# EasyBMS.net
KiCad netlist of a schematic drawn in EAGLE
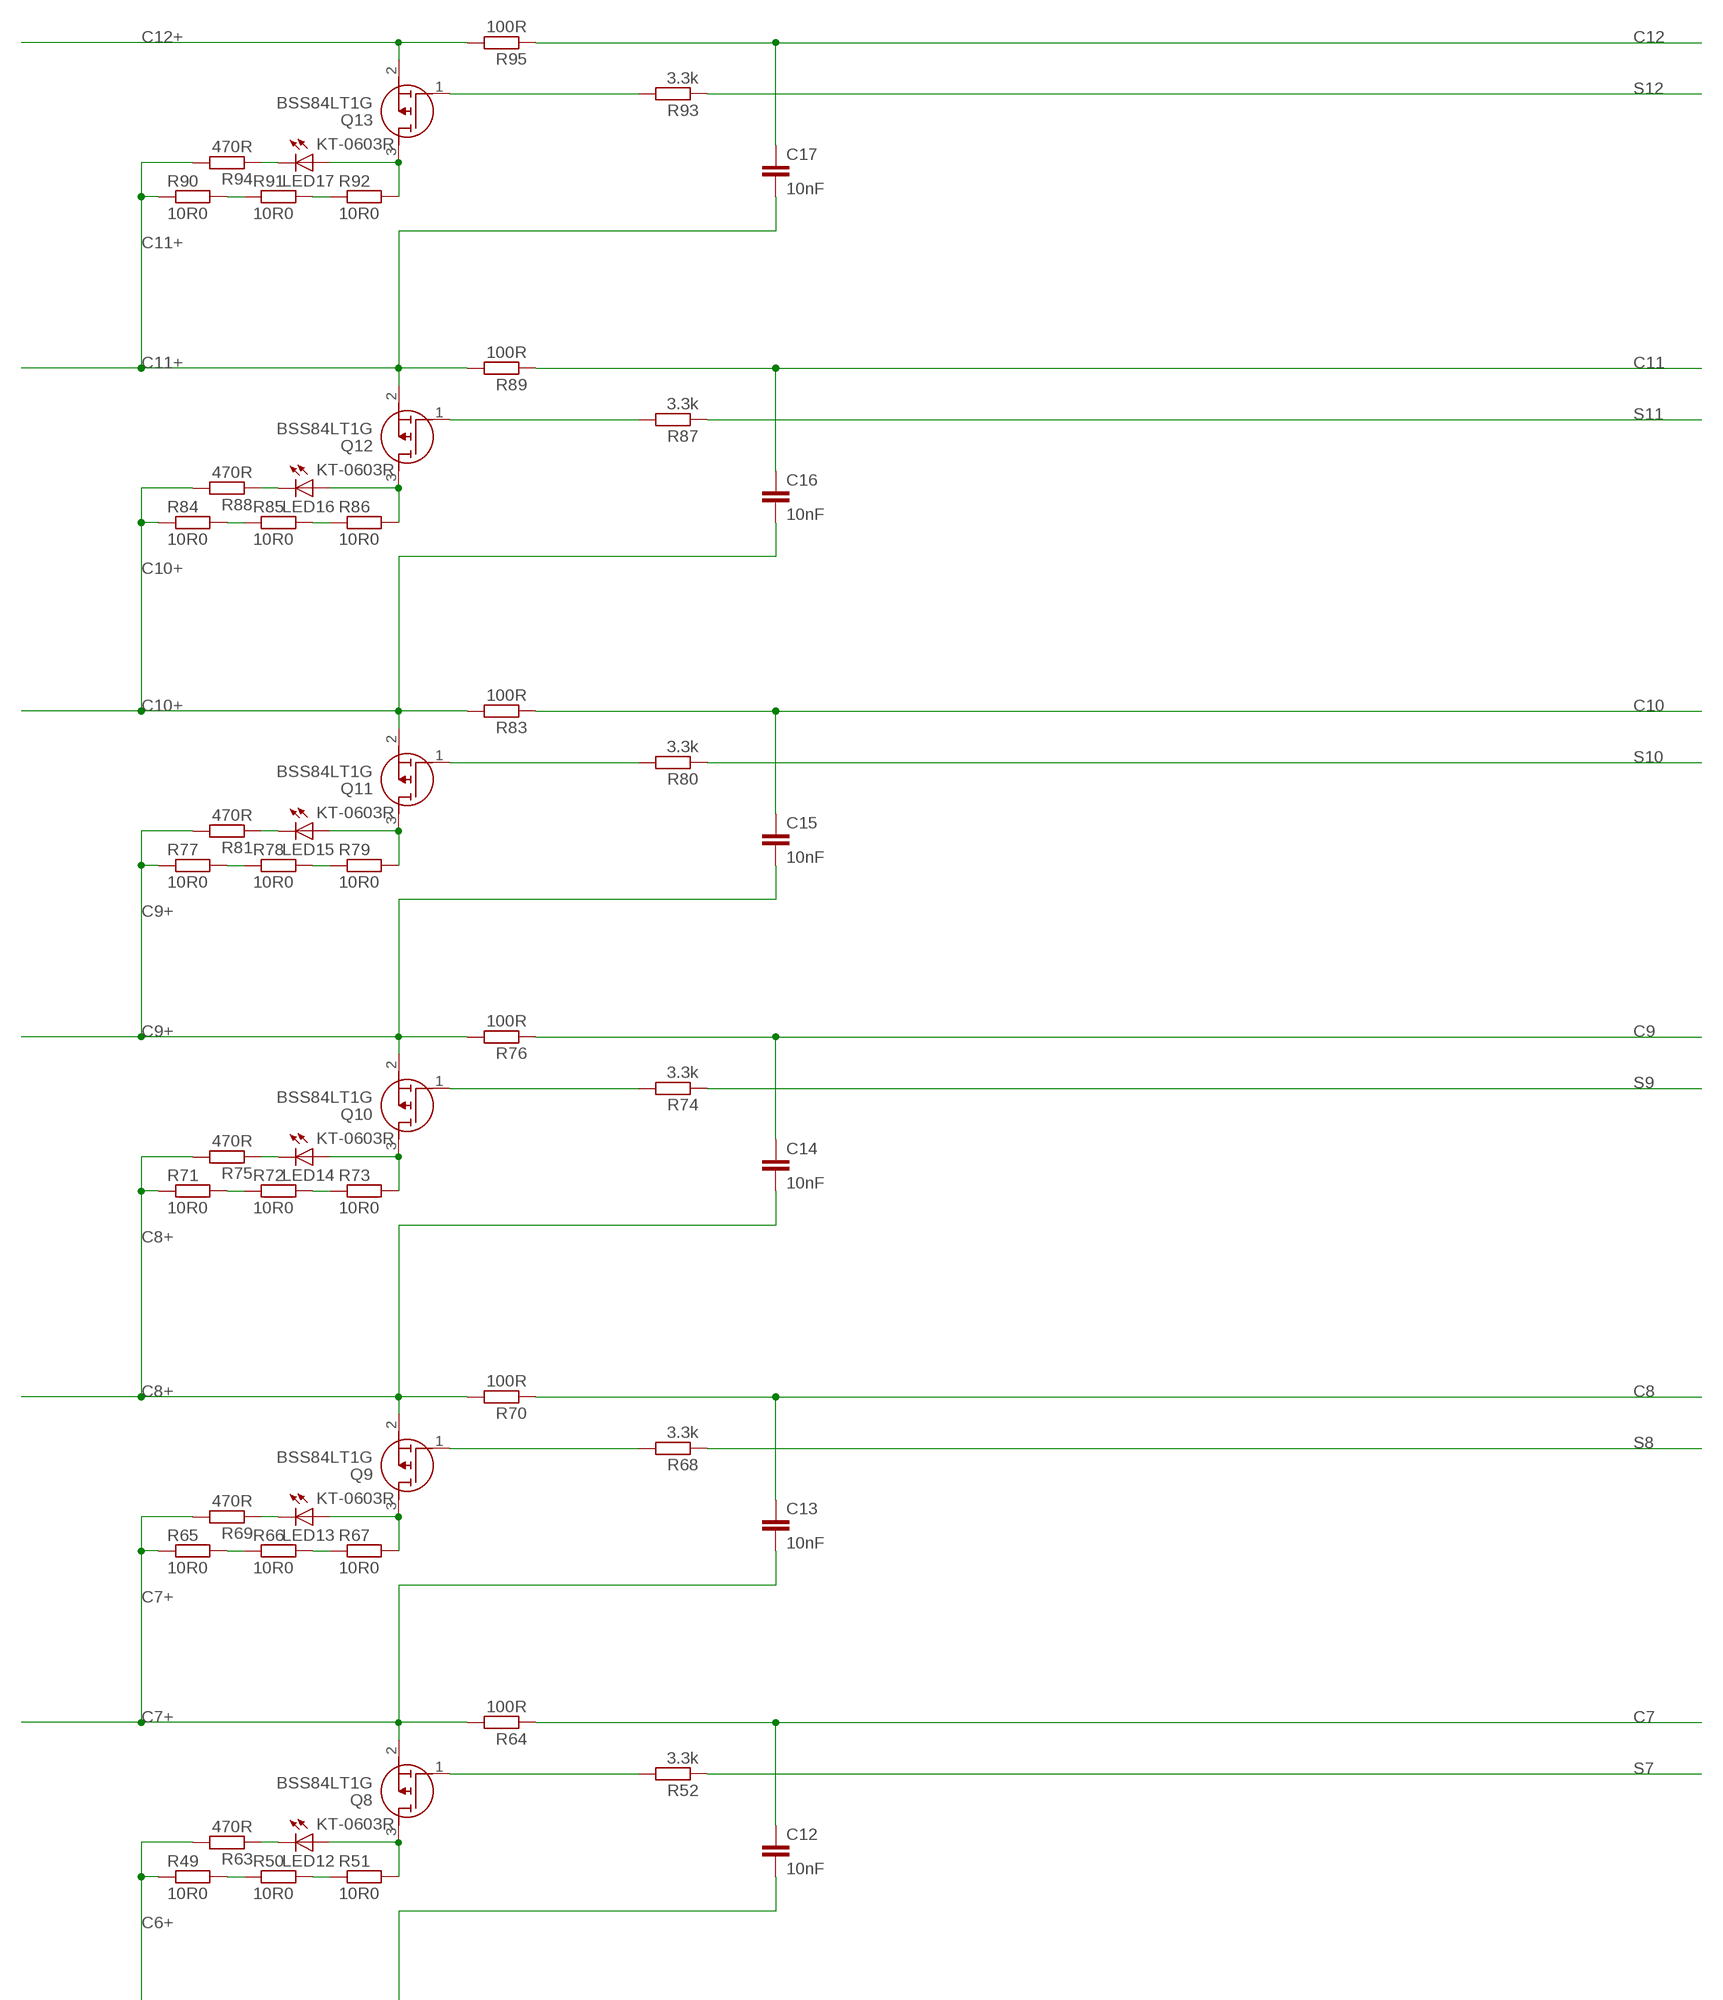
[diagram p0: schematic, sheet 1, part 1 of 3]
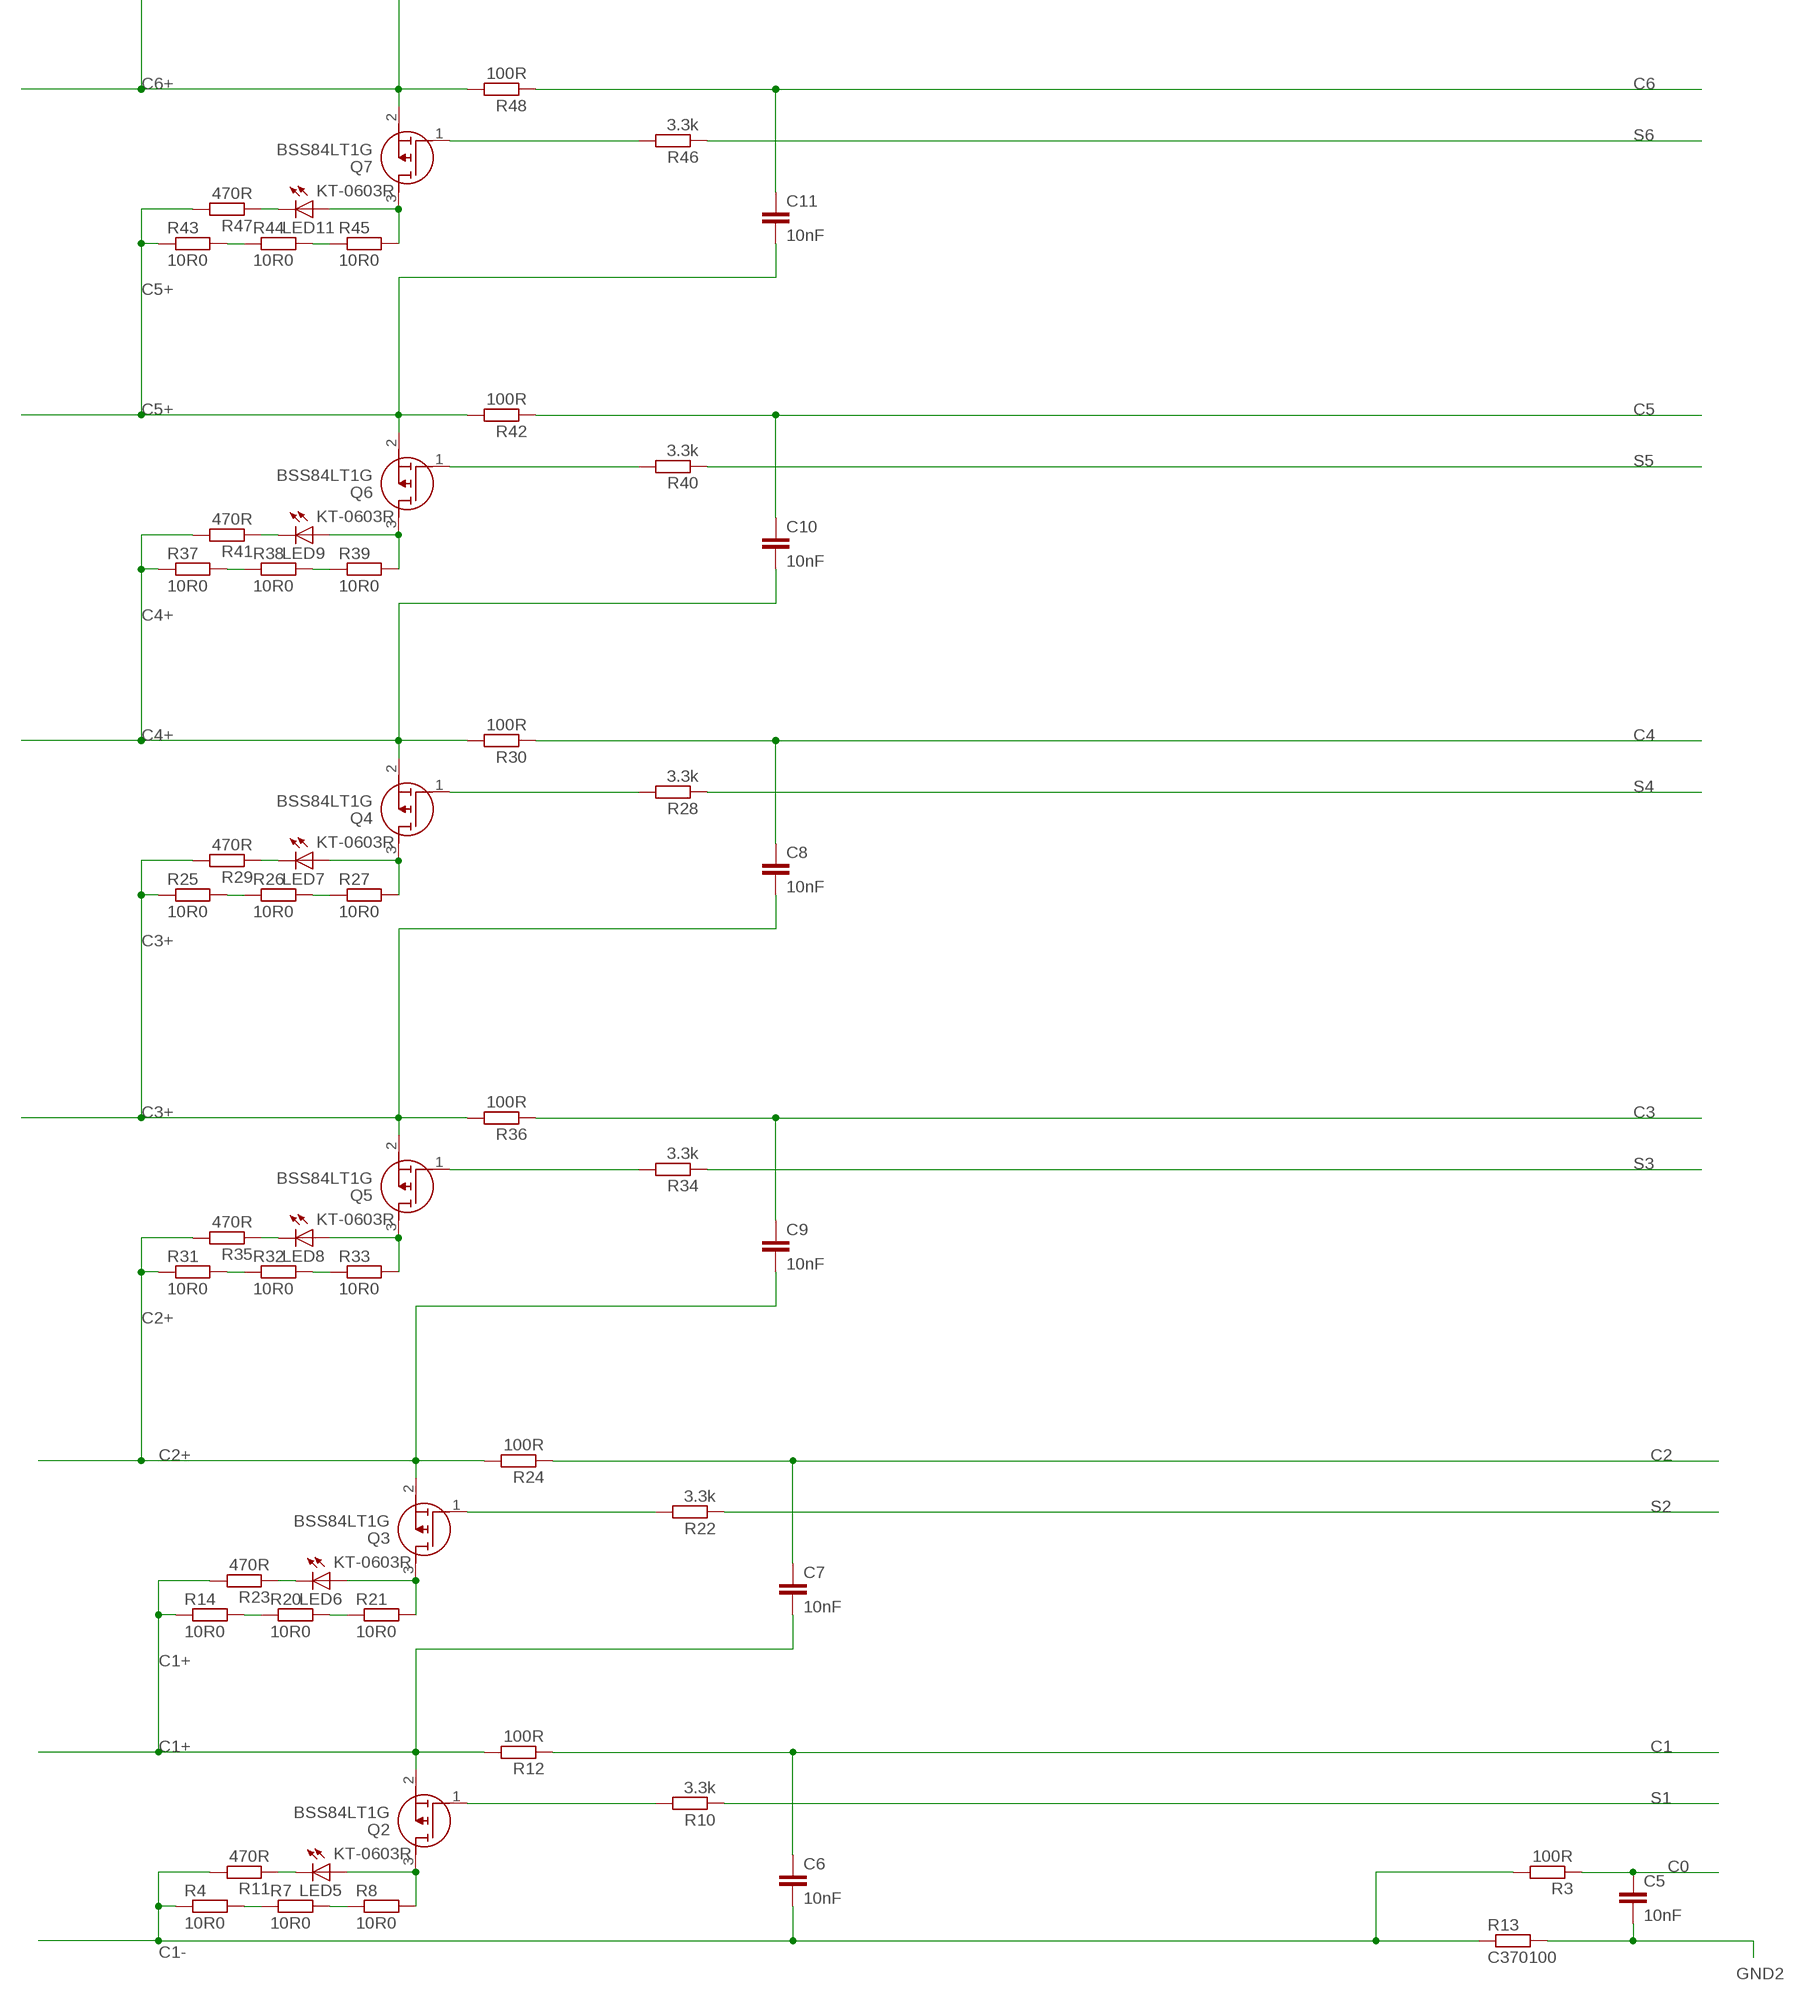
[diagram p1: schematic, sheet 1, part 2 of 3]
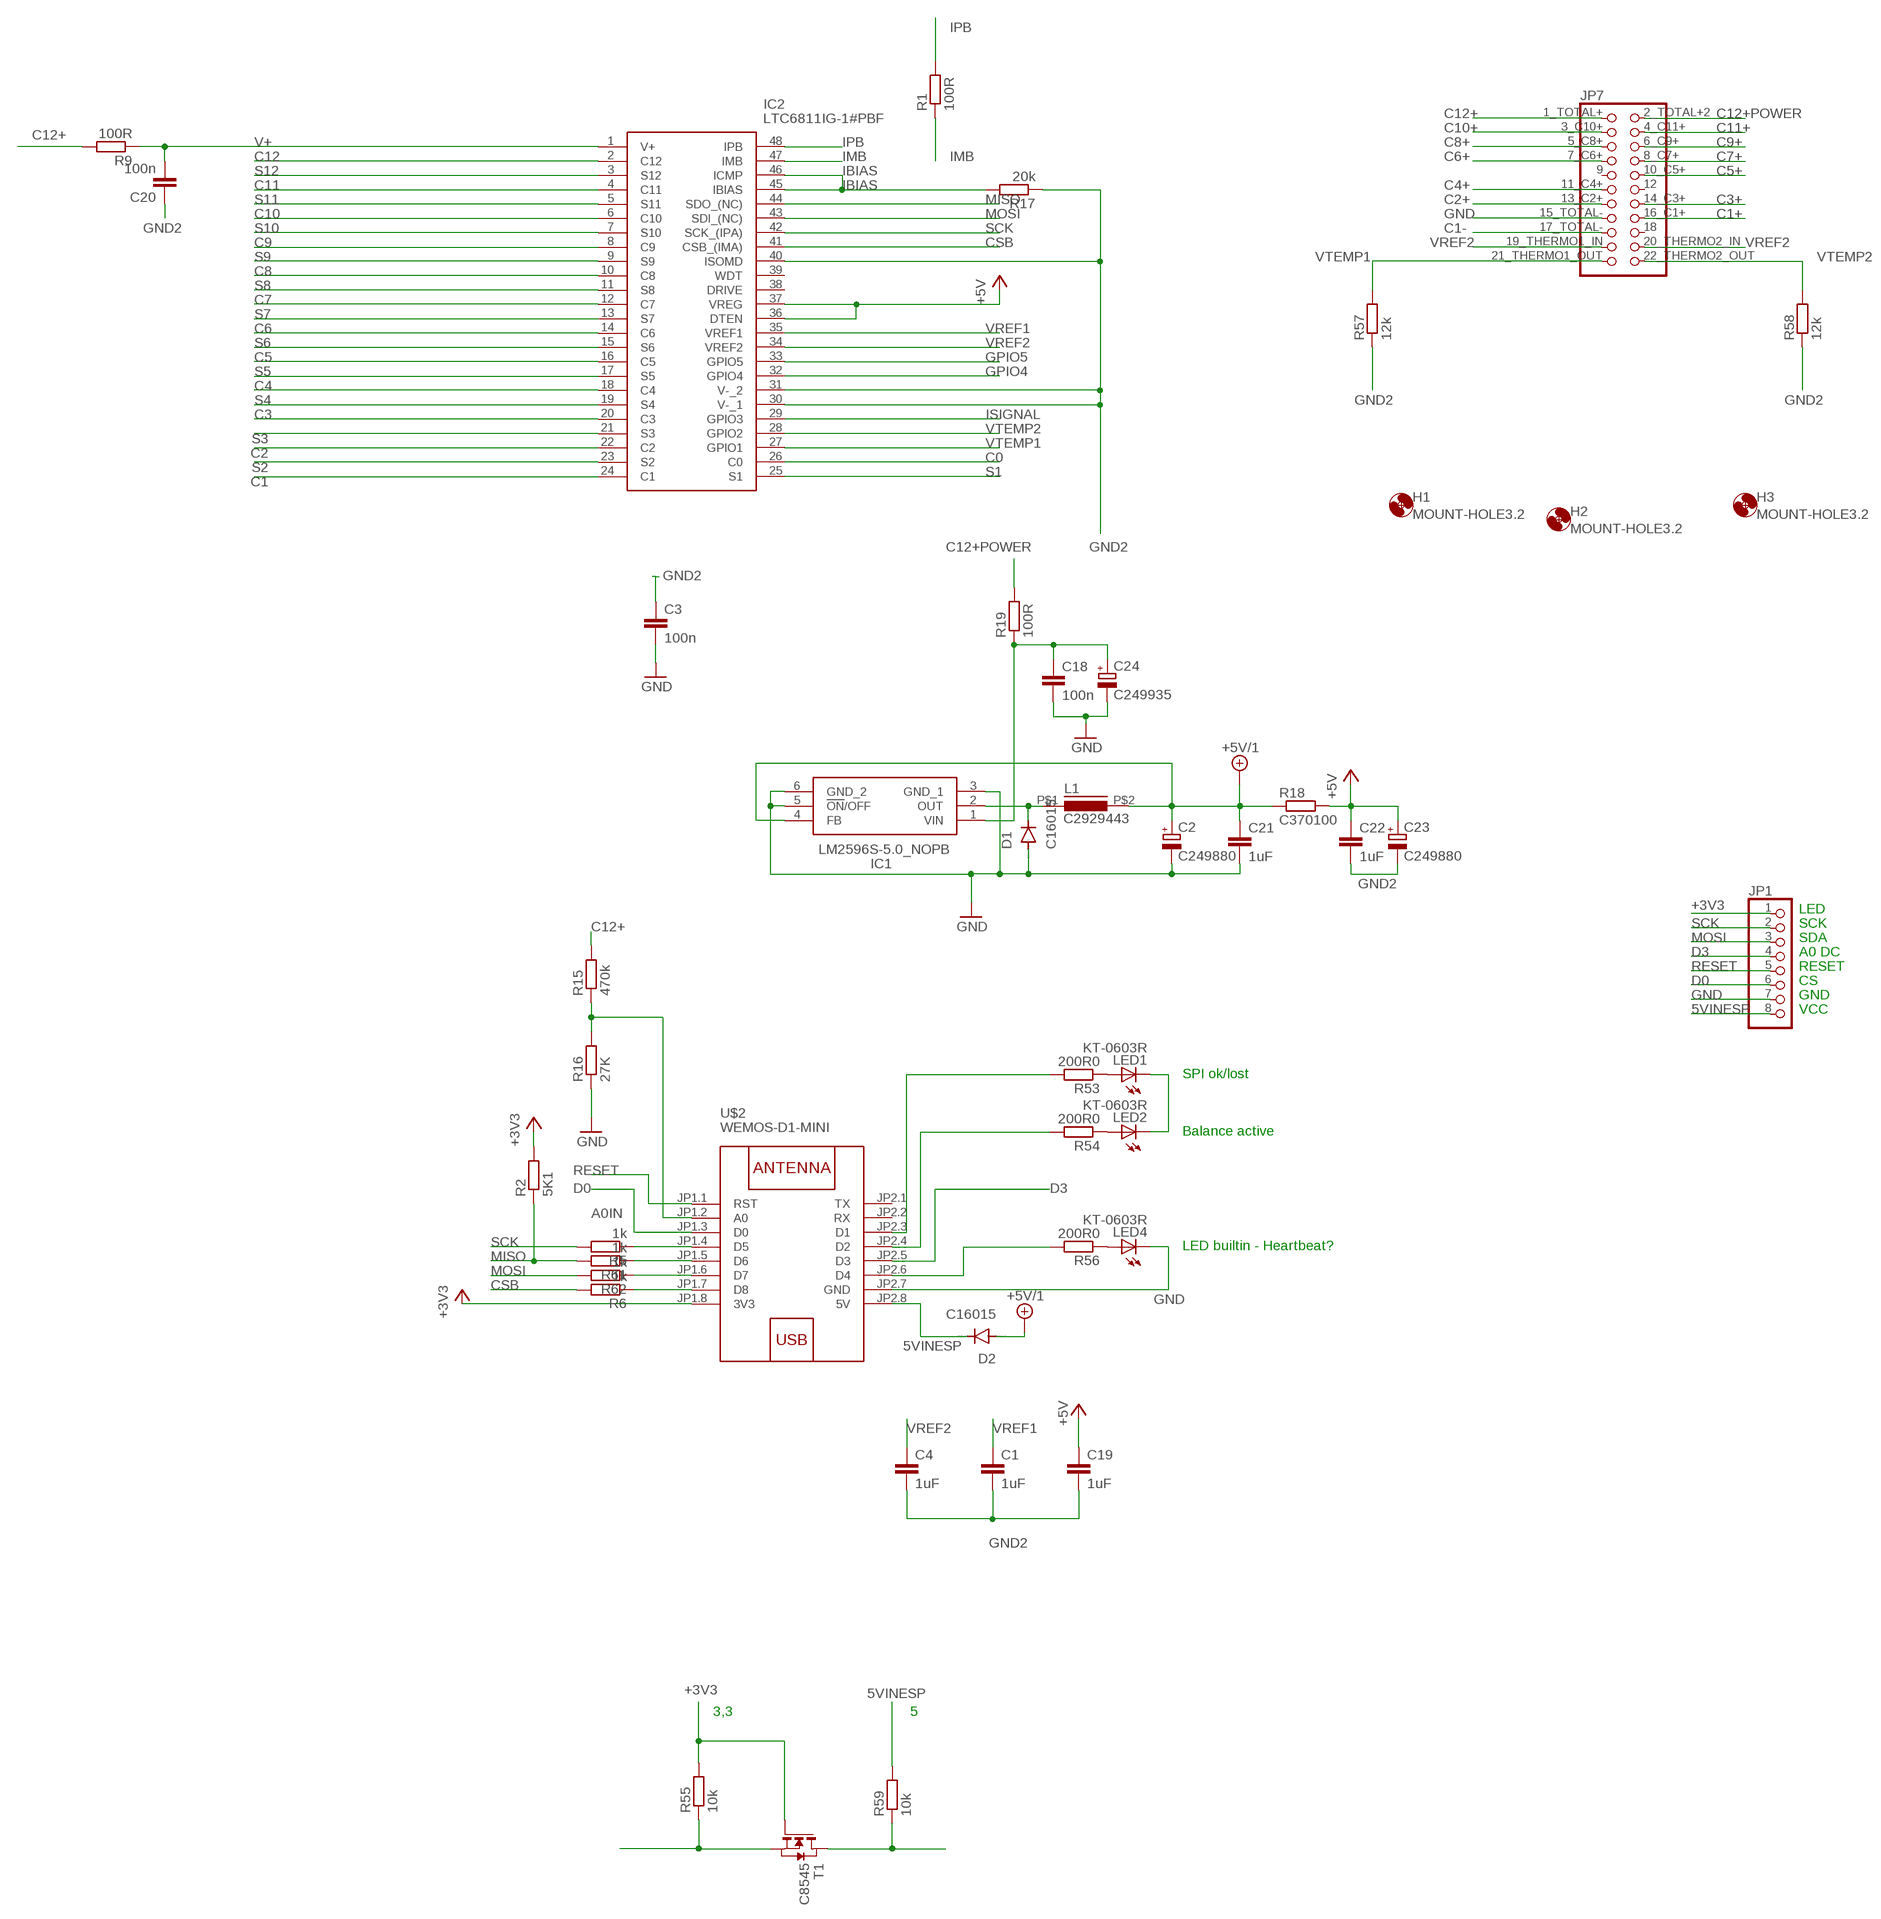
[diagram p2: schematic, sheet 1, part 3 of 3]

(export (version "E")
  (design (tool "Eeschema 10.0.6"))
  (components
    (comp (ref "C1")
      (value "1uF")
      (footprint "eagle-import:C1206")
      (libsource (lib "eagle-import") (part "C-EUC1206"))
    )
    (comp (ref "C2")
      (value "C249880")
      (footprint "eagle-import:UD-8X10_NICHICON")
      (libsource (lib "eagle-import") (part "CPOL-EUUD-8X10"))
    )
    (comp (ref "C3")
      (value "100n")
      (footprint "eagle-import:C0402")
      (libsource (lib "eagle-import") (part "C-EUC0402"))
    )
    (comp (ref "C4")
      (value "1uF")
      (footprint "eagle-import:C1206")
      (libsource (lib "eagle-import") (part "C-EUC1206"))
    )
    (comp (ref "C5")
      (value "10nF")
      (footprint "eagle-import:C0402")
      (libsource (lib "eagle-import") (part "C-EUC0402"))
    )
    (comp (ref "C6")
      (value "10nF")
      (footprint "eagle-import:C0402")
      (libsource (lib "eagle-import") (part "C-EUC0402"))
    )
    (comp (ref "C7")
      (value "10nF")
      (footprint "eagle-import:C0402")
      (libsource (lib "eagle-import") (part "C-EUC0402"))
    )
    (comp (ref "C8")
      (value "10nF")
      (footprint "eagle-import:C0402")
      (libsource (lib "eagle-import") (part "C-EUC0402"))
    )
    (comp (ref "C9")
      (value "10nF")
      (footprint "eagle-import:C0402")
      (libsource (lib "eagle-import") (part "C-EUC0402"))
    )
    (comp (ref "C10")
      (value "10nF")
      (footprint "eagle-import:C0402")
      (libsource (lib "eagle-import") (part "C-EUC0402"))
    )
    (comp (ref "C11")
      (value "10nF")
      (footprint "eagle-import:C0402")
      (libsource (lib "eagle-import") (part "C-EUC0402"))
    )
    (comp (ref "C12")
      (value "10nF")
      (footprint "eagle-import:C0402")
      (libsource (lib "eagle-import") (part "C-EUC0402"))
    )
    (comp (ref "C13")
      (value "10nF")
      (footprint "eagle-import:C0402")
      (libsource (lib "eagle-import") (part "C-EUC0402"))
    )
    (comp (ref "C14")
      (value "10nF")
      (footprint "eagle-import:C0402")
      (libsource (lib "eagle-import") (part "C-EUC0402"))
    )
    (comp (ref "C15")
      (value "10nF")
      (footprint "eagle-import:C0402")
      (libsource (lib "eagle-import") (part "C-EUC0402"))
    )
    (comp (ref "C16")
      (value "10nF")
      (footprint "eagle-import:C0402")
      (libsource (lib "eagle-import") (part "C-EUC0402"))
    )
    (comp (ref "C17")
      (value "10nF")
      (footprint "eagle-import:C0402")
      (libsource (lib "eagle-import") (part "C-EUC0402"))
    )
    (comp (ref "C18")
      (value "100n")
      (footprint "eagle-import:C0402")
      (libsource (lib "eagle-import") (part "C-EUC0402"))
    )
    (comp (ref "C19")
      (value "1uF")
      (footprint "eagle-import:C1206")
      (libsource (lib "eagle-import") (part "C-EUC1206"))
    )
    (comp (ref "C20")
      (value "100n")
      (footprint "eagle-import:C0402")
      (libsource (lib "eagle-import") (part "C-EUC0402"))
    )
    (comp (ref "C21")
      (value "1uF")
      (footprint "eagle-import:C1206")
      (libsource (lib "eagle-import") (part "C-EUC1206"))
    )
    (comp (ref "C22")
      (value "1uF")
      (footprint "eagle-import:C1206")
      (libsource (lib "eagle-import") (part "C-EUC1206"))
    )
    (comp (ref "C23")
      (value "C249880")
      (footprint "eagle-import:UD-8X10_NICHICON")
      (libsource (lib "eagle-import") (part "CPOL-EUUD-8X10"))
    )
    (comp (ref "C24")
      (value "C249935")
      (footprint "eagle-import:WCAP-ASLI_16X17(DXL)")
      (libsource (lib "eagle-import") (part "VZH471M1JTR-1616"))
    )
    (comp (ref "D1")
      (value "C16015")
      (footprint "eagle-import:DO214AC")
      (libsource (lib "eagle-import") (part "DIODE-DO214AC"))
    )
    (comp (ref "D2")
      (value "C16015")
      (footprint "eagle-import:DO214AC")
      (libsource (lib "eagle-import") (part "DIODE-DO214AC"))
    )
    (comp (ref "H1")
      (value "MOUNT-HOLE3.2")
      (footprint "eagle-import:3,2")
      (libsource (lib "eagle-import") (part "MOUNT-HOLE3.2"))
    )
    (comp (ref "H2")
      (value "MOUNT-HOLE3.2")
      (footprint "eagle-import:3,2")
      (libsource (lib "eagle-import") (part "MOUNT-HOLE3.2"))
    )
    (comp (ref "H3")
      (value "MOUNT-HOLE3.2")
      (footprint "eagle-import:3,2")
      (libsource (lib "eagle-import") (part "MOUNT-HOLE3.2"))
    )
    (comp (ref "IC1")
      (value "LM2596S-5.0_NOPB")
      (footprint "eagle-import:KTT0005B")
      (fields
        (field (name "MANUFACTURER_PART_NUMBER") "LM2596S-5.0/NOPB")
        (field (name "MOUSER_PART_NUMBER") "926-LM2596S-5.0/NOPB")
      )
      (libsource (lib "eagle-import") (part "LM2596S-5.0_NOPB"))
    )
    (comp (ref "IC2")
      (value "LTC6811IG-1#PBF")
      (footprint "eagle-import:SOP50P780X200-48N")
      (fields (field (name "MOUSER_PART_NUMBER") "584-LTC6811IG-1#PBF"))
      (libsource (lib "eagle-import") (part "LTC6811IG-1#PBF"))
    )
    (comp (ref "JP1")
      (value "PINHD-1X8")
      (footprint "eagle-import:1X08")
      (libsource (lib "eagle-import") (part "PINHD-1X8"))
    )
    (comp (ref "JP7")
      (value "PINHD-2X11_MEB12S")
      (footprint "eagle-import:2X11_MEB12S")
      (libsource (lib "eagle-import") (part "PINHD-2X11_MEB12S"))
    )
    (comp (ref "L1")
      (value "C2929443")
      (footprint "eagle-import:CY75-100UH")
      (libsource (lib "eagle-import") (part "CY75-100UH"))
    )
    (comp (ref "LED1")
      (value "KT-0603R")
      (footprint "eagle-import:CHIPLED_0603")
      (libsource (lib "eagle-import") (part "LEDCHIPLED_0603"))
    )
    (comp (ref "LED2")
      (value "KT-0603R")
      (footprint "eagle-import:CHIPLED_0603")
      (libsource (lib "eagle-import") (part "LEDCHIPLED_0603"))
    )
    (comp (ref "LED4")
      (value "KT-0603R")
      (footprint "eagle-import:CHIPLED_0603")
      (libsource (lib "eagle-import") (part "LEDCHIPLED_0603"))
    )
    (comp (ref "LED5")
      (value "KT-0603R")
      (footprint "eagle-import:CHIPLED_0603")
      (libsource (lib "eagle-import") (part "LEDCHIPLED_0603"))
    )
    (comp (ref "LED6")
      (value "KT-0603R")
      (footprint "eagle-import:CHIPLED_0603")
      (libsource (lib "eagle-import") (part "LEDCHIPLED_0603"))
    )
    (comp (ref "LED7")
      (value "KT-0603R")
      (footprint "eagle-import:CHIPLED_0603")
      (libsource (lib "eagle-import") (part "LEDCHIPLED_0603"))
    )
    (comp (ref "LED8")
      (value "KT-0603R")
      (footprint "eagle-import:CHIPLED_0603")
      (libsource (lib "eagle-import") (part "LEDCHIPLED_0603"))
    )
    (comp (ref "LED9")
      (value "KT-0603R")
      (footprint "eagle-import:CHIPLED_0603")
      (libsource (lib "eagle-import") (part "LEDCHIPLED_0603"))
    )
    (comp (ref "LED11")
      (value "KT-0603R")
      (footprint "eagle-import:CHIPLED_0603")
      (libsource (lib "eagle-import") (part "LEDCHIPLED_0603"))
    )
    (comp (ref "LED12")
      (value "KT-0603R")
      (footprint "eagle-import:CHIPLED_0603")
      (libsource (lib "eagle-import") (part "LEDCHIPLED_0603"))
    )
    (comp (ref "LED13")
      (value "KT-0603R")
      (footprint "eagle-import:CHIPLED_0603")
      (libsource (lib "eagle-import") (part "LEDCHIPLED_0603"))
    )
    (comp (ref "LED14")
      (value "KT-0603R")
      (footprint "eagle-import:CHIPLED_0603")
      (libsource (lib "eagle-import") (part "LEDCHIPLED_0603"))
    )
    (comp (ref "LED15")
      (value "KT-0603R")
      (footprint "eagle-import:CHIPLED_0603")
      (libsource (lib "eagle-import") (part "LEDCHIPLED_0603"))
    )
    (comp (ref "LED16")
      (value "KT-0603R")
      (footprint "eagle-import:CHIPLED_0603")
      (libsource (lib "eagle-import") (part "LEDCHIPLED_0603"))
    )
    (comp (ref "LED17")
      (value "KT-0603R")
      (footprint "eagle-import:CHIPLED_0603")
      (libsource (lib "eagle-import") (part "LEDCHIPLED_0603"))
    )
    (comp (ref "Q2")
      (value "BSS84LT1G")
      (footprint "eagle-import:SOT96P237X111-3N")
      (fields (field (name "MOUSER_PART_NUMBER") "863-BSS84LT1G"))
      (libsource (lib "eagle-import") (part "BSS84LT1G"))
    )
    (comp (ref "Q3")
      (value "BSS84LT1G")
      (footprint "eagle-import:SOT96P237X111-3N")
      (fields (field (name "MOUSER_PART_NUMBER") "863-BSS84LT1G"))
      (libsource (lib "eagle-import") (part "BSS84LT1G"))
    )
    (comp (ref "Q4")
      (value "BSS84LT1G")
      (footprint "eagle-import:SOT96P237X111-3N")
      (fields (field (name "MOUSER_PART_NUMBER") "863-BSS84LT1G"))
      (libsource (lib "eagle-import") (part "BSS84LT1G"))
    )
    (comp (ref "Q5")
      (value "BSS84LT1G")
      (footprint "eagle-import:SOT96P237X111-3N")
      (fields (field (name "MOUSER_PART_NUMBER") "863-BSS84LT1G"))
      (libsource (lib "eagle-import") (part "BSS84LT1G"))
    )
    (comp (ref "Q6")
      (value "BSS84LT1G")
      (footprint "eagle-import:SOT96P237X111-3N")
      (fields (field (name "MOUSER_PART_NUMBER") "863-BSS84LT1G"))
      (libsource (lib "eagle-import") (part "BSS84LT1G"))
    )
    (comp (ref "Q7")
      (value "BSS84LT1G")
      (footprint "eagle-import:SOT96P237X111-3N")
      (fields (field (name "MOUSER_PART_NUMBER") "863-BSS84LT1G"))
      (libsource (lib "eagle-import") (part "BSS84LT1G"))
    )
    (comp (ref "Q8")
      (value "BSS84LT1G")
      (footprint "eagle-import:SOT96P237X111-3N")
      (fields (field (name "MOUSER_PART_NUMBER") "863-BSS84LT1G"))
      (libsource (lib "eagle-import") (part "BSS84LT1G"))
    )
    (comp (ref "Q9")
      (value "BSS84LT1G")
      (footprint "eagle-import:SOT96P237X111-3N")
      (fields (field (name "MOUSER_PART_NUMBER") "863-BSS84LT1G"))
      (libsource (lib "eagle-import") (part "BSS84LT1G"))
    )
    (comp (ref "Q10")
      (value "BSS84LT1G")
      (footprint "eagle-import:SOT96P237X111-3N")
      (fields (field (name "MOUSER_PART_NUMBER") "863-BSS84LT1G"))
      (libsource (lib "eagle-import") (part "BSS84LT1G"))
    )
    (comp (ref "Q11")
      (value "BSS84LT1G")
      (footprint "eagle-import:SOT96P237X111-3N")
      (fields (field (name "MOUSER_PART_NUMBER") "863-BSS84LT1G"))
      (libsource (lib "eagle-import") (part "BSS84LT1G"))
    )
    (comp (ref "Q12")
      (value "BSS84LT1G")
      (footprint "eagle-import:SOT96P237X111-3N")
      (fields (field (name "MOUSER_PART_NUMBER") "863-BSS84LT1G"))
      (libsource (lib "eagle-import") (part "BSS84LT1G"))
    )
    (comp (ref "Q13")
      (value "BSS84LT1G")
      (footprint "eagle-import:SOT96P237X111-3N")
      (fields (field (name "MOUSER_PART_NUMBER") "863-BSS84LT1G"))
      (libsource (lib "eagle-import") (part "BSS84LT1G"))
    )
    (comp (ref "R1")
      (value "100R")
      (footprint "eagle-import:R0603")
      (libsource (lib "eagle-import") (part "R-EU_R0603"))
    )
    (comp (ref "R2")
      (value "5K1")
      (footprint "eagle-import:R0603")
      (libsource (lib "eagle-import") (part "R-EU_R0603"))
    )
    (comp (ref "R3")
      (value "100R")
      (footprint "eagle-import:R0402")
      (libsource (lib "eagle-import") (part "R-EU_R0402"))
    )
    (comp (ref "R4")
      (value "10R0")
      (footprint "eagle-import:R1206")
      (libsource (lib "eagle-import") (part "R-EU_R1206"))
    )
    (comp (ref "R5")
      (value "1k")
      (footprint "eagle-import:R0603")
      (libsource (lib "eagle-import") (part "R-EU_R0603"))
    )
    (comp (ref "R6")
      (value "1k")
      (footprint "eagle-import:R0603")
      (libsource (lib "eagle-import") (part "R-EU_R0603"))
    )
    (comp (ref "R7")
      (value "10R0")
      (footprint "eagle-import:R1206")
      (libsource (lib "eagle-import") (part "R-EU_R1206"))
    )
    (comp (ref "R8")
      (value "10R0")
      (footprint "eagle-import:R1206")
      (libsource (lib "eagle-import") (part "R-EU_R1206"))
    )
    (comp (ref "R9")
      (value "100R")
      (footprint "eagle-import:R0402")
      (libsource (lib "eagle-import") (part "R-EU_R0402"))
    )
    (comp (ref "R10")
      (value "3.3k")
      (footprint "eagle-import:R0402")
      (libsource (lib "eagle-import") (part "R-EU_R0402"))
    )
    (comp (ref "R11")
      (value "470R")
      (footprint "eagle-import:R0402")
      (libsource (lib "eagle-import") (part "R-EU_R0402"))
    )
    (comp (ref "R12")
      (value "100R")
      (footprint "eagle-import:R0402")
      (libsource (lib "eagle-import") (part "R-EU_R0402"))
    )
    (comp (ref "R13")
      (value "C370100")
      (footprint "eagle-import:R1206")
      (libsource (lib "eagle-import") (part "R-EU_R1206"))
    )
    (comp (ref "R14")
      (value "10R0")
      (footprint "eagle-import:R1206")
      (libsource (lib "eagle-import") (part "R-EU_R1206"))
    )
    (comp (ref "R15")
      (value "470k")
      (footprint "eagle-import:R0603")
      (libsource (lib "eagle-import") (part "R-EU_R0603"))
    )
    (comp (ref "R16")
      (value "27K")
      (footprint "eagle-import:R0603")
      (libsource (lib "eagle-import") (part "R-EU_R0603"))
    )
    (comp (ref "R17")
      (value "20k")
      (footprint "eagle-import:R0603")
      (libsource (lib "eagle-import") (part "R-EU_R0603"))
    )
    (comp (ref "R18")
      (value "C370100")
      (footprint "eagle-import:R1206")
      (libsource (lib "eagle-import") (part "R-EU_R1206"))
    )
    (comp (ref "R19")
      (value "100R")
      (footprint "eagle-import:R1206")
      (libsource (lib "eagle-import") (part "R-EU_R1206"))
    )
    (comp (ref "R20")
      (value "10R0")
      (footprint "eagle-import:R1206")
      (libsource (lib "eagle-import") (part "R-EU_R1206"))
    )
    (comp (ref "R21")
      (value "10R0")
      (footprint "eagle-import:R1206")
      (libsource (lib "eagle-import") (part "R-EU_R1206"))
    )
    (comp (ref "R22")
      (value "3.3k")
      (footprint "eagle-import:R0402")
      (libsource (lib "eagle-import") (part "R-EU_R0402"))
    )
    (comp (ref "R23")
      (value "470R")
      (footprint "eagle-import:R0402")
      (libsource (lib "eagle-import") (part "R-EU_R0402"))
    )
    (comp (ref "R24")
      (value "100R")
      (footprint "eagle-import:R0402")
      (libsource (lib "eagle-import") (part "R-EU_R0402"))
    )
    (comp (ref "R25")
      (value "10R0")
      (footprint "eagle-import:R1206")
      (libsource (lib "eagle-import") (part "R-EU_R1206"))
    )
    (comp (ref "R26")
      (value "10R0")
      (footprint "eagle-import:R1206")
      (libsource (lib "eagle-import") (part "R-EU_R1206"))
    )
    (comp (ref "R27")
      (value "10R0")
      (footprint "eagle-import:R1206")
      (libsource (lib "eagle-import") (part "R-EU_R1206"))
    )
    (comp (ref "R28")
      (value "3.3k")
      (footprint "eagle-import:R0402")
      (libsource (lib "eagle-import") (part "R-EU_R0402"))
    )
    (comp (ref "R29")
      (value "470R")
      (footprint "eagle-import:R0402")
      (libsource (lib "eagle-import") (part "R-EU_R0402"))
    )
    (comp (ref "R30")
      (value "100R")
      (footprint "eagle-import:R0402")
      (libsource (lib "eagle-import") (part "R-EU_R0402"))
    )
    (comp (ref "R31")
      (value "10R0")
      (footprint "eagle-import:R1206")
      (libsource (lib "eagle-import") (part "R-EU_R1206"))
    )
    (comp (ref "R32")
      (value "10R0")
      (footprint "eagle-import:R1206")
      (libsource (lib "eagle-import") (part "R-EU_R1206"))
    )
    (comp (ref "R33")
      (value "10R0")
      (footprint "eagle-import:R1206")
      (libsource (lib "eagle-import") (part "R-EU_R1206"))
    )
    (comp (ref "R34")
      (value "3.3k")
      (footprint "eagle-import:R0402")
      (libsource (lib "eagle-import") (part "R-EU_R0402"))
    )
    (comp (ref "R35")
      (value "470R")
      (footprint "eagle-import:R0402")
      (libsource (lib "eagle-import") (part "R-EU_R0402"))
    )
    (comp (ref "R36")
      (value "100R")
      (footprint "eagle-import:R0402")
      (libsource (lib "eagle-import") (part "R-EU_R0402"))
    )
    (comp (ref "R37")
      (value "10R0")
      (footprint "eagle-import:R1206")
      (libsource (lib "eagle-import") (part "R-EU_R1206"))
    )
    (comp (ref "R38")
      (value "10R0")
      (footprint "eagle-import:R1206")
      (libsource (lib "eagle-import") (part "R-EU_R1206"))
    )
    (comp (ref "R39")
      (value "10R0")
      (footprint "eagle-import:R1206")
      (libsource (lib "eagle-import") (part "R-EU_R1206"))
    )
    (comp (ref "R40")
      (value "3.3k")
      (footprint "eagle-import:R0402")
      (libsource (lib "eagle-import") (part "R-EU_R0402"))
    )
    (comp (ref "R41")
      (value "470R")
      (footprint "eagle-import:R0402")
      (libsource (lib "eagle-import") (part "R-EU_R0402"))
    )
    (comp (ref "R42")
      (value "100R")
      (footprint "eagle-import:R0402")
      (libsource (lib "eagle-import") (part "R-EU_R0402"))
    )
    (comp (ref "R43")
      (value "10R0")
      (footprint "eagle-import:R1206")
      (libsource (lib "eagle-import") (part "R-EU_R1206"))
    )
    (comp (ref "R44")
      (value "10R0")
      (footprint "eagle-import:R1206")
      (libsource (lib "eagle-import") (part "R-EU_R1206"))
    )
    (comp (ref "R45")
      (value "10R0")
      (footprint "eagle-import:R1206")
      (libsource (lib "eagle-import") (part "R-EU_R1206"))
    )
    (comp (ref "R46")
      (value "3.3k")
      (footprint "eagle-import:R0402")
      (libsource (lib "eagle-import") (part "R-EU_R0402"))
    )
    (comp (ref "R47")
      (value "470R")
      (footprint "eagle-import:R0402")
      (libsource (lib "eagle-import") (part "R-EU_R0402"))
    )
    (comp (ref "R48")
      (value "100R")
      (footprint "eagle-import:R0402")
      (libsource (lib "eagle-import") (part "R-EU_R0402"))
    )
    (comp (ref "R49")
      (value "10R0")
      (footprint "eagle-import:R1206")
      (libsource (lib "eagle-import") (part "R-EU_R1206"))
    )
    (comp (ref "R50")
      (value "10R0")
      (footprint "eagle-import:R1206")
      (libsource (lib "eagle-import") (part "R-EU_R1206"))
    )
    (comp (ref "R51")
      (value "10R0")
      (footprint "eagle-import:R1206")
      (libsource (lib "eagle-import") (part "R-EU_R1206"))
    )
    (comp (ref "R52")
      (value "3.3k")
      (footprint "eagle-import:R0402")
      (libsource (lib "eagle-import") (part "R-EU_R0402"))
    )
    (comp (ref "R53")
      (value "200R0")
      (footprint "eagle-import:R0603")
      (libsource (lib "eagle-import") (part "R-EU_R0603"))
    )
    (comp (ref "R54")
      (value "200R0")
      (footprint "eagle-import:R0603")
      (libsource (lib "eagle-import") (part "R-EU_R0603"))
    )
    (comp (ref "R55")
      (value "10k")
      (footprint "eagle-import:R0603")
      (libsource (lib "eagle-import") (part "R-EU_R0603"))
    )
    (comp (ref "R56")
      (value "200R0")
      (footprint "eagle-import:R0603")
      (libsource (lib "eagle-import") (part "R-EU_R0603"))
    )
    (comp (ref "R57")
      (value "12k")
      (footprint "eagle-import:R0603")
      (libsource (lib "eagle-import") (part "R-EU_R0603"))
    )
    (comp (ref "R58")
      (value "12k")
      (footprint "eagle-import:R0603")
      (libsource (lib "eagle-import") (part "R-EU_R0603"))
    )
    (comp (ref "R59")
      (value "10k")
      (footprint "eagle-import:R0603")
      (libsource (lib "eagle-import") (part "R-EU_R0603"))
    )
    (comp (ref "R61")
      (value "1k")
      (footprint "eagle-import:R0603")
      (libsource (lib "eagle-import") (part "R-EU_R0603"))
    )
    (comp (ref "R62")
      (value "1k")
      (footprint "eagle-import:R0603")
      (libsource (lib "eagle-import") (part "R-EU_R0603"))
    )
    (comp (ref "R63")
      (value "470R")
      (footprint "eagle-import:R0402")
      (libsource (lib "eagle-import") (part "R-EU_R0402"))
    )
    (comp (ref "R64")
      (value "100R")
      (footprint "eagle-import:R0402")
      (libsource (lib "eagle-import") (part "R-EU_R0402"))
    )
    (comp (ref "R65")
      (value "10R0")
      (footprint "eagle-import:R1206")
      (libsource (lib "eagle-import") (part "R-EU_R1206"))
    )
    (comp (ref "R66")
      (value "10R0")
      (footprint "eagle-import:R1206")
      (libsource (lib "eagle-import") (part "R-EU_R1206"))
    )
    (comp (ref "R67")
      (value "10R0")
      (footprint "eagle-import:R1206")
      (libsource (lib "eagle-import") (part "R-EU_R1206"))
    )
    (comp (ref "R68")
      (value "3.3k")
      (footprint "eagle-import:R0402")
      (libsource (lib "eagle-import") (part "R-EU_R0402"))
    )
    (comp (ref "R69")
      (value "470R")
      (footprint "eagle-import:R0402")
      (libsource (lib "eagle-import") (part "R-EU_R0402"))
    )
    (comp (ref "R70")
      (value "100R")
      (footprint "eagle-import:R0402")
      (libsource (lib "eagle-import") (part "R-EU_R0402"))
    )
    (comp (ref "R71")
      (value "10R0")
      (footprint "eagle-import:R1206")
      (libsource (lib "eagle-import") (part "R-EU_R1206"))
    )
    (comp (ref "R72")
      (value "10R0")
      (footprint "eagle-import:R1206")
      (libsource (lib "eagle-import") (part "R-EU_R1206"))
    )
    (comp (ref "R73")
      (value "10R0")
      (footprint "eagle-import:R1206")
      (libsource (lib "eagle-import") (part "R-EU_R1206"))
    )
    (comp (ref "R74")
      (value "3.3k")
      (footprint "eagle-import:R0402")
      (libsource (lib "eagle-import") (part "R-EU_R0402"))
    )
    (comp (ref "R75")
      (value "470R")
      (footprint "eagle-import:R0402")
      (libsource (lib "eagle-import") (part "R-EU_R0402"))
    )
    (comp (ref "R76")
      (value "100R")
      (footprint "eagle-import:R0402")
      (libsource (lib "eagle-import") (part "R-EU_R0402"))
    )
    (comp (ref "R77")
      (value "10R0")
      (footprint "eagle-import:R1206")
      (libsource (lib "eagle-import") (part "R-EU_R1206"))
    )
    (comp (ref "R78")
      (value "10R0")
      (footprint "eagle-import:R1206")
      (libsource (lib "eagle-import") (part "R-EU_R1206"))
    )
    (comp (ref "R79")
      (value "10R0")
      (footprint "eagle-import:R1206")
      (libsource (lib "eagle-import") (part "R-EU_R1206"))
    )
    (comp (ref "R80")
      (value "3.3k")
      (footprint "eagle-import:R0402")
      (libsource (lib "eagle-import") (part "R-EU_R0402"))
    )
    (comp (ref "R81")
      (value "470R")
      (footprint "eagle-import:R0402")
      (libsource (lib "eagle-import") (part "R-EU_R0402"))
    )
    (comp (ref "R83")
      (value "100R")
      (footprint "eagle-import:R0402")
      (libsource (lib "eagle-import") (part "R-EU_R0402"))
    )
    (comp (ref "R84")
      (value "10R0")
      (footprint "eagle-import:R1206")
      (libsource (lib "eagle-import") (part "R-EU_R1206"))
    )
    (comp (ref "R85")
      (value "10R0")
      (footprint "eagle-import:R1206")
      (libsource (lib "eagle-import") (part "R-EU_R1206"))
    )
    (comp (ref "R86")
      (value "10R0")
      (footprint "eagle-import:R1206")
      (libsource (lib "eagle-import") (part "R-EU_R1206"))
    )
    (comp (ref "R87")
      (value "3.3k")
      (footprint "eagle-import:R0402")
      (libsource (lib "eagle-import") (part "R-EU_R0402"))
    )
    (comp (ref "R88")
      (value "470R")
      (footprint "eagle-import:R0402")
      (libsource (lib "eagle-import") (part "R-EU_R0402"))
    )
    (comp (ref "R89")
      (value "100R")
      (footprint "eagle-import:R0402")
      (libsource (lib "eagle-import") (part "R-EU_R0402"))
    )
    (comp (ref "R90")
      (value "10R0")
      (footprint "eagle-import:R1206")
      (libsource (lib "eagle-import") (part "R-EU_R1206"))
    )
    (comp (ref "R91")
      (value "10R0")
      (footprint "eagle-import:R1206")
      (libsource (lib "eagle-import") (part "R-EU_R1206"))
    )
    (comp (ref "R92")
      (value "10R0")
      (footprint "eagle-import:R1206")
      (libsource (lib "eagle-import") (part "R-EU_R1206"))
    )
    (comp (ref "R93")
      (value "3.3k")
      (footprint "eagle-import:R0402")
      (libsource (lib "eagle-import") (part "R-EU_R0402"))
    )
    (comp (ref "R94")
      (value "470R")
      (footprint "eagle-import:R0402")
      (libsource (lib "eagle-import") (part "R-EU_R0402"))
    )
    (comp (ref "R95")
      (value "100R")
      (footprint "eagle-import:R0402")
      (libsource (lib "eagle-import") (part "R-EU_R0402"))
    )
    (comp (ref "T1")
      (value "C8545")
      (footprint "eagle-import:SOT-23")
      (libsource (lib "eagle-import") (part "NMOSSOT23"))
    )
    (comp (ref "U$2")
      (value "WEMOS-D1-MINI")
      (footprint "eagle-import:WEMOS-D1-MINI")
      (libsource (lib "eagle-import") (part "WEMOS-D1-MINI"))
    )
  )
  (nets
    (net (code "1") (name "+3V3") (class "Default")
      (node (ref "JP1") (pin "1") (pinfunction "1_1") (pintype "passive"))
      (node (ref "R2") (pin "2") (pinfunction "2_2") (pintype "passive"))
      (node (ref "R55") (pin "2") (pinfunction "2_2") (pintype "passive"))
      (node (ref "T1") (pin "3") (pinfunction "G_3") (pintype "passive"))
      (node (ref "U$2") (pin "JP1.8") (pinfunction "3V3_JP1.8") (pintype "power_in"))
    )
    (net (code "2") (name "+5V") (class "Default")
      (node (ref "C19") (pin "1") (pinfunction "1_1") (pintype "passive"))
      (node (ref "C22") (pin "1") (pinfunction "1_1") (pintype "passive"))
      (node (ref "C23") (pin "+") (pinfunction "+_+") (pintype "passive"))
      (node (ref "IC2") (pin "36") (pinfunction "DTEN_36") (pintype "bidirectional"))
      (node (ref "IC2") (pin "37") (pinfunction "VREG_37") (pintype "bidirectional"))
      (node (ref "R18") (pin "2") (pinfunction "2_2") (pintype "passive"))
    )
    (net (code "3") (name "+5V{slash}1") (class "Default")
      (node (ref "C2") (pin "+") (pinfunction "+_+") (pintype "passive"))
      (node (ref "C21") (pin "1") (pinfunction "1_1") (pintype "passive"))
      (node (ref "D2") (pin "A") (pinfunction "A_A") (pintype "passive"))
      (node (ref "IC1") (pin "4") (pinfunction "FB_4") (pintype "bidirectional"))
      (node (ref "L1") (pin "P$2") (pinfunction "2_P$2") (pintype "passive"))
      (node (ref "R18") (pin "1") (pinfunction "1_1") (pintype "passive"))
    )
    (net (code "4") (name "/5VINESP") (class "Default")
      (node (ref "D2") (pin "C") (pinfunction "C_C") (pintype "passive"))
      (node (ref "JP1") (pin "8") (pinfunction "8_8") (pintype "passive"))
      (node (ref "R59") (pin "2") (pinfunction "2_2") (pintype "passive"))
      (node (ref "U$2") (pin "JP2.8") (pinfunction "5V_JP2.8") (pintype "power_in"))
    )
    (net (code "5") (name "/A0IN") (class "Default")
      (node (ref "R15") (pin "1") (pinfunction "1_1") (pintype "passive"))
      (node (ref "R16") (pin "2") (pinfunction "2_2") (pintype "passive"))
      (node (ref "U$2") (pin "JP1.2") (pinfunction "A0_JP1.2") (pintype "bidirectional"))
    )
    (net (code "6") (name "/C0") (class "Default")
      (node (ref "C5") (pin "1") (pinfunction "1_1") (pintype "passive"))
      (node (ref "IC2") (pin "26") (pinfunction "C0_26") (pintype "bidirectional"))
      (node (ref "R3") (pin "1") (pinfunction "1_1") (pintype "passive"))
    )
    (net (code "7") (name "/C1") (class "Default")
      (node (ref "C6") (pin "1") (pinfunction "1_1") (pintype "passive"))
      (node (ref "IC2") (pin "24") (pinfunction "C1_24") (pintype "bidirectional"))
      (node (ref "R12") (pin "1") (pinfunction "1_1") (pintype "passive"))
    )
    (net (code "8") (name "/C1+") (class "Default")
      (node (ref "C7") (pin "2") (pinfunction "2_2") (pintype "passive"))
      (node (ref "JP7") (pin "16_C1+") (pinfunction "16_C1+_16_C1+") (pintype "passive"))
      (node (ref "Q2") (pin "2") (pinfunction "S_2") (pintype "bidirectional"))
      (node (ref "R12") (pin "2") (pinfunction "2_2") (pintype "passive"))
      (node (ref "R14") (pin "1") (pinfunction "1_1") (pintype "passive"))
      (node (ref "R23") (pin "2") (pinfunction "2_2") (pintype "passive"))
    )
    (net (code "9") (name "/C1-") (class "Default")
      (node (ref "C6") (pin "2") (pinfunction "2_2") (pintype "passive"))
      (node (ref "JP7") (pin "17_TOTAL-") (pinfunction "TOTAL-_17_TOTAL-") (pintype "passive"))
      (node (ref "R11") (pin "2") (pinfunction "2_2") (pintype "passive"))
      (node (ref "R13") (pin "1") (pinfunction "1_1") (pintype "passive"))
      (node (ref "R3") (pin "2") (pinfunction "2_2") (pintype "passive"))
      (node (ref "R4") (pin "1") (pinfunction "1_1") (pintype "passive"))
    )
    (net (code "10") (name "/C2") (class "Default")
      (node (ref "C7") (pin "1") (pinfunction "1_1") (pintype "passive"))
      (node (ref "IC2") (pin "22") (pinfunction "C2_22") (pintype "bidirectional"))
      (node (ref "R24") (pin "1") (pinfunction "1_1") (pintype "passive"))
    )
    (net (code "11") (name "/C2+") (class "Default")
      (node (ref "C9") (pin "2") (pinfunction "2_2") (pintype "passive"))
      (node (ref "JP7") (pin "13_C2+") (pinfunction "13_C2+_13_C2+") (pintype "passive"))
      (node (ref "Q3") (pin "2") (pinfunction "S_2") (pintype "bidirectional"))
      (node (ref "R24") (pin "2") (pinfunction "2_2") (pintype "passive"))
      (node (ref "R31") (pin "1") (pinfunction "1_1") (pintype "passive"))
      (node (ref "R35") (pin "2") (pinfunction "2_2") (pintype "passive"))
    )
    (net (code "12") (name "/C3") (class "Default")
      (node (ref "C9") (pin "1") (pinfunction "1_1") (pintype "passive"))
      (node (ref "IC2") (pin "20") (pinfunction "C3_20") (pintype "bidirectional"))
      (node (ref "R36") (pin "1") (pinfunction "1_1") (pintype "passive"))
    )
    (net (code "13") (name "/C3+") (class "Default")
      (node (ref "C8") (pin "2") (pinfunction "2_2") (pintype "passive"))
      (node (ref "JP7") (pin "14_C3+") (pinfunction "14_C3+_14_C3+") (pintype "passive"))
      (node (ref "Q5") (pin "2") (pinfunction "S_2") (pintype "bidirectional"))
      (node (ref "R25") (pin "1") (pinfunction "1_1") (pintype "passive"))
      (node (ref "R29") (pin "2") (pinfunction "2_2") (pintype "passive"))
      (node (ref "R36") (pin "2") (pinfunction "2_2") (pintype "passive"))
    )
    (net (code "14") (name "/C4") (class "Default")
      (node (ref "C8") (pin "1") (pinfunction "1_1") (pintype "passive"))
      (node (ref "IC2") (pin "18") (pinfunction "C4_18") (pintype "bidirectional"))
      (node (ref "R30") (pin "1") (pinfunction "1_1") (pintype "passive"))
    )
    (net (code "15") (name "/C4+") (class "Default")
      (node (ref "C10") (pin "2") (pinfunction "2_2") (pintype "passive"))
      (node (ref "JP7") (pin "11_C4+") (pinfunction "11_C4+_11_C4+") (pintype "passive"))
      (node (ref "Q4") (pin "2") (pinfunction "S_2") (pintype "bidirectional"))
      (node (ref "R30") (pin "2") (pinfunction "2_2") (pintype "passive"))
      (node (ref "R37") (pin "1") (pinfunction "1_1") (pintype "passive"))
      (node (ref "R41") (pin "2") (pinfunction "2_2") (pintype "passive"))
    )
    (net (code "16") (name "/C5") (class "Default")
      (node (ref "C10") (pin "1") (pinfunction "1_1") (pintype "passive"))
      (node (ref "IC2") (pin "16") (pinfunction "C5_16") (pintype "bidirectional"))
      (node (ref "R42") (pin "1") (pinfunction "1_1") (pintype "passive"))
    )
    (net (code "17") (name "/C5+") (class "Default")
      (node (ref "C11") (pin "2") (pinfunction "2_2") (pintype "passive"))
      (node (ref "JP7") (pin "10_C5+") (pinfunction "10_C5+_10_C5+") (pintype "passive"))
      (node (ref "Q6") (pin "2") (pinfunction "S_2") (pintype "bidirectional"))
      (node (ref "R42") (pin "2") (pinfunction "2_2") (pintype "passive"))
      (node (ref "R43") (pin "1") (pinfunction "1_1") (pintype "passive"))
      (node (ref "R47") (pin "2") (pinfunction "2_2") (pintype "passive"))
    )
    (net (code "18") (name "/C6") (class "Default")
      (node (ref "C11") (pin "1") (pinfunction "1_1") (pintype "passive"))
      (node (ref "IC2") (pin "14") (pinfunction "C6_14") (pintype "bidirectional"))
      (node (ref "R48") (pin "1") (pinfunction "1_1") (pintype "passive"))
    )
    (net (code "19") (name "/C6+") (class "Default")
      (node (ref "C12") (pin "2") (pinfunction "2_2") (pintype "passive"))
      (node (ref "JP7") (pin "7_C6+") (pinfunction "7_C6+_7_C6+") (pintype "passive"))
      (node (ref "Q7") (pin "2") (pinfunction "S_2") (pintype "bidirectional"))
      (node (ref "R48") (pin "2") (pinfunction "2_2") (pintype "passive"))
      (node (ref "R49") (pin "1") (pinfunction "1_1") (pintype "passive"))
      (node (ref "R63") (pin "2") (pinfunction "2_2") (pintype "passive"))
    )
    (net (code "20") (name "/C7") (class "Default")
      (node (ref "C12") (pin "1") (pinfunction "1_1") (pintype "passive"))
      (node (ref "IC2") (pin "12") (pinfunction "C7_12") (pintype "bidirectional"))
      (node (ref "R64") (pin "1") (pinfunction "1_1") (pintype "passive"))
    )
    (net (code "21") (name "/C7+") (class "Default")
      (node (ref "C13") (pin "2") (pinfunction "2_2") (pintype "passive"))
      (node (ref "JP7") (pin "8_C7+") (pinfunction "8_C7+_8_C7+") (pintype "passive"))
      (node (ref "Q8") (pin "2") (pinfunction "S_2") (pintype "bidirectional"))
      (node (ref "R64") (pin "2") (pinfunction "2_2") (pintype "passive"))
      (node (ref "R65") (pin "1") (pinfunction "1_1") (pintype "passive"))
      (node (ref "R69") (pin "2") (pinfunction "2_2") (pintype "passive"))
    )
    (net (code "22") (name "/C8") (class "Default")
      (node (ref "C13") (pin "1") (pinfunction "1_1") (pintype "passive"))
      (node (ref "IC2") (pin "10") (pinfunction "C8_10") (pintype "bidirectional"))
      (node (ref "R70") (pin "1") (pinfunction "1_1") (pintype "passive"))
    )
    (net (code "23") (name "/C8+") (class "Default")
      (node (ref "C14") (pin "2") (pinfunction "2_2") (pintype "passive"))
      (node (ref "JP7") (pin "5_C8+") (pinfunction "5_C8+_5_C8+") (pintype "passive"))
      (node (ref "Q9") (pin "2") (pinfunction "S_2") (pintype "bidirectional"))
      (node (ref "R70") (pin "2") (pinfunction "2_2") (pintype "passive"))
      (node (ref "R71") (pin "1") (pinfunction "1_1") (pintype "passive"))
      (node (ref "R75") (pin "2") (pinfunction "2_2") (pintype "passive"))
    )
    (net (code "24") (name "/C9") (class "Default")
      (node (ref "C14") (pin "1") (pinfunction "1_1") (pintype "passive"))
      (node (ref "IC2") (pin "8") (pinfunction "C9_8") (pintype "bidirectional"))
      (node (ref "R76") (pin "1") (pinfunction "1_1") (pintype "passive"))
    )
    (net (code "25") (name "/C9+") (class "Default")
      (node (ref "C15") (pin "2") (pinfunction "2_2") (pintype "passive"))
      (node (ref "JP7") (pin "6_C9+") (pinfunction "6_C9+_6_C9+") (pintype "passive"))
      (node (ref "Q10") (pin "2") (pinfunction "S_2") (pintype "bidirectional"))
      (node (ref "R76") (pin "2") (pinfunction "2_2") (pintype "passive"))
      (node (ref "R77") (pin "1") (pinfunction "1_1") (pintype "passive"))
      (node (ref "R81") (pin "2") (pinfunction "2_2") (pintype "passive"))
    )
    (net (code "26") (name "/C10") (class "Default")
      (node (ref "C15") (pin "1") (pinfunction "1_1") (pintype "passive"))
      (node (ref "IC2") (pin "6") (pinfunction "C10_6") (pintype "bidirectional"))
      (node (ref "R83") (pin "1") (pinfunction "1_1") (pintype "passive"))
    )
    (net (code "27") (name "/C10+") (class "Default")
      (node (ref "C16") (pin "2") (pinfunction "2_2") (pintype "passive"))
      (node (ref "JP7") (pin "3_C10+") (pinfunction "3_C10+_3_C10+") (pintype "passive"))
      (node (ref "Q11") (pin "2") (pinfunction "S_2") (pintype "bidirectional"))
      (node (ref "R83") (pin "2") (pinfunction "2_2") (pintype "passive"))
      (node (ref "R84") (pin "1") (pinfunction "1_1") (pintype "passive"))
      (node (ref "R88") (pin "2") (pinfunction "2_2") (pintype "passive"))
    )
    (net (code "28") (name "/C11") (class "Default")
      (node (ref "C16") (pin "1") (pinfunction "1_1") (pintype "passive"))
      (node (ref "IC2") (pin "4") (pinfunction "C11_4") (pintype "bidirectional"))
      (node (ref "R89") (pin "1") (pinfunction "1_1") (pintype "passive"))
    )
    (net (code "29") (name "/C11+") (class "Default")
      (node (ref "C17") (pin "2") (pinfunction "2_2") (pintype "passive"))
      (node (ref "JP7") (pin "4_C11+") (pinfunction "4_C11+_4_C11+") (pintype "passive"))
      (node (ref "Q12") (pin "2") (pinfunction "S_2") (pintype "bidirectional"))
      (node (ref "R89") (pin "2") (pinfunction "2_2") (pintype "passive"))
      (node (ref "R90") (pin "1") (pinfunction "1_1") (pintype "passive"))
      (node (ref "R94") (pin "2") (pinfunction "2_2") (pintype "passive"))
    )
    (net (code "30") (name "/C12") (class "Default")
      (node (ref "C17") (pin "1") (pinfunction "1_1") (pintype "passive"))
      (node (ref "IC2") (pin "2") (pinfunction "C12_2") (pintype "bidirectional"))
      (node (ref "R95") (pin "1") (pinfunction "1_1") (pintype "passive"))
    )
    (net (code "31") (name "/C12+") (class "Default")
      (node (ref "JP7") (pin "1_TOTAL+") (pinfunction "1_TOTAL+_1_TOTAL+") (pintype "passive"))
      (node (ref "Q13") (pin "2") (pinfunction "S_2") (pintype "bidirectional"))
      (node (ref "R15") (pin "2") (pinfunction "2_2") (pintype "passive"))
      (node (ref "R9") (pin "2") (pinfunction "2_2") (pintype "passive"))
      (node (ref "R95") (pin "2") (pinfunction "2_2") (pintype "passive"))
    )
    (net (code "32") (name "/C12+POWER") (class "Default")
      (node (ref "JP7") (pin "2_TOTAL+2") (pinfunction "2_CTOTAL+_2_TOTAL+2") (pintype "passive"))
      (node (ref "R19") (pin "2") (pinfunction "2_2") (pintype "passive"))
    )
    (net (code "33") (name "/CSB") (class "Default")
      (node (ref "IC2") (pin "41") (pinfunction "CSB_(IMA)_41") (pintype "bidirectional"))
      (node (ref "R6") (pin "2") (pinfunction "2_2") (pintype "passive"))
    )
    (net (code "34") (name "/D0") (class "Default")
      (node (ref "JP1") (pin "6") (pinfunction "6_6") (pintype "passive"))
      (node (ref "U$2") (pin "JP1.3") (pinfunction "D0_JP1.3") (pintype "bidirectional"))
    )
    (net (code "35") (name "/D3") (class "Default")
      (node (ref "JP1") (pin "4") (pinfunction "4_4") (pintype "passive"))
      (node (ref "U$2") (pin "JP2.5") (pinfunction "D3_JP2.5") (pintype "bidirectional"))
    )
    (net (code "36") (name "/GND2") (class "Default")
      (node (ref "C1") (pin "2") (pinfunction "2_2") (pintype "passive"))
      (node (ref "C19") (pin "2") (pinfunction "2_2") (pintype "passive"))
      (node (ref "C20") (pin "1") (pinfunction "1_1") (pintype "passive"))
      (node (ref "C22") (pin "2") (pinfunction "2_2") (pintype "passive"))
      (node (ref "C23") (pin "-") (pinfunction "-_-") (pintype "passive"))
      (node (ref "C3") (pin "1") (pinfunction "1_1") (pintype "passive"))
      (node (ref "C4") (pin "2") (pinfunction "2_2") (pintype "passive"))
      (node (ref "C5") (pin "2") (pinfunction "2_2") (pintype "passive"))
      (node (ref "IC2") (pin "30") (pinfunction "V-_1_30") (pintype "bidirectional"))
      (node (ref "IC2") (pin "31") (pinfunction "V-_2_31") (pintype "bidirectional"))
      (node (ref "IC2") (pin "40") (pinfunction "ISOMD_40") (pintype "bidirectional"))
      (node (ref "R13") (pin "2") (pinfunction "2_2") (pintype "passive"))
      (node (ref "R17") (pin "1") (pinfunction "1_1") (pintype "passive"))
      (node (ref "R57") (pin "1") (pinfunction "1_1") (pintype "passive"))
      (node (ref "R58") (pin "1") (pinfunction "1_1") (pintype "passive"))
    )
    (net (code "37") (name "/GPIO4") (class "Default")
      (node (ref "IC2") (pin "32") (pinfunction "GPIO4_32") (pintype "bidirectional"))
    )
    (net (code "38") (name "/GPIO5") (class "Default")
      (node (ref "IC2") (pin "33") (pinfunction "GPIO5_33") (pintype "bidirectional"))
    )
    (net (code "39") (name "/IBIAS") (class "Default")
      (node (ref "IC2") (pin "45") (pinfunction "IBIAS_45") (pintype "bidirectional"))
      (node (ref "IC2") (pin "46") (pinfunction "ICMP_46") (pintype "bidirectional"))
      (node (ref "R17") (pin "2") (pinfunction "2_2") (pintype "passive"))
    )
    (net (code "40") (name "/IMB") (class "Default")
      (node (ref "IC2") (pin "47") (pinfunction "IMB_47") (pintype "bidirectional"))
      (node (ref "R1") (pin "1") (pinfunction "1_1") (pintype "passive"))
    )
    (net (code "41") (name "/IPB") (class "Default")
      (node (ref "IC2") (pin "48") (pinfunction "IPB_48") (pintype "bidirectional"))
      (node (ref "R1") (pin "2") (pinfunction "2_2") (pintype "passive"))
    )
    (net (code "42") (name "/ISIGNAL") (class "Default")
      (node (ref "IC2") (pin "29") (pinfunction "GPIO3_29") (pintype "bidirectional"))
    )
    (net (code "43") (name "/MISO") (class "Default")
      (node (ref "IC2") (pin "44") (pinfunction "SDO_(NC)_44") (pintype "bidirectional"))
      (node (ref "R2") (pin "1") (pinfunction "1_1") (pintype "passive"))
      (node (ref "R61") (pin "2") (pinfunction "2_2") (pintype "passive"))
    )
    (net (code "44") (name "/MOSI") (class "Default")
      (node (ref "IC2") (pin "43") (pinfunction "SDI_(NC)_43") (pintype "bidirectional"))
      (node (ref "JP1") (pin "3") (pinfunction "3_3") (pintype "passive"))
      (node (ref "R62") (pin "2") (pinfunction "2_2") (pintype "passive"))
    )
    (net (code "45") (name "/RESET") (class "Default")
      (node (ref "JP1") (pin "5") (pinfunction "5_5") (pintype "passive"))
      (node (ref "U$2") (pin "JP1.1") (pinfunction "RST_JP1.1") (pintype "bidirectional"))
    )
    (net (code "46") (name "/S1") (class "Default")
      (node (ref "IC2") (pin "25") (pinfunction "S1_25") (pintype "bidirectional"))
      (node (ref "R10") (pin "1") (pinfunction "1_1") (pintype "passive"))
    )
    (net (code "47") (name "/S2") (class "Default")
      (node (ref "IC2") (pin "23") (pinfunction "S2_23") (pintype "bidirectional"))
      (node (ref "R22") (pin "1") (pinfunction "1_1") (pintype "passive"))
    )
    (net (code "48") (name "/S3") (class "Default")
      (node (ref "IC2") (pin "21") (pinfunction "S3_21") (pintype "bidirectional"))
      (node (ref "R34") (pin "1") (pinfunction "1_1") (pintype "passive"))
    )
    (net (code "49") (name "/S4") (class "Default")
      (node (ref "IC2") (pin "19") (pinfunction "S4_19") (pintype "bidirectional"))
      (node (ref "R28") (pin "1") (pinfunction "1_1") (pintype "passive"))
    )
    (net (code "50") (name "/S5") (class "Default")
      (node (ref "IC2") (pin "17") (pinfunction "S5_17") (pintype "bidirectional"))
      (node (ref "R40") (pin "1") (pinfunction "1_1") (pintype "passive"))
    )
    (net (code "51") (name "/S6") (class "Default")
      (node (ref "IC2") (pin "15") (pinfunction "S6_15") (pintype "bidirectional"))
      (node (ref "R46") (pin "1") (pinfunction "1_1") (pintype "passive"))
    )
    (net (code "52") (name "/S7") (class "Default")
      (node (ref "IC2") (pin "13") (pinfunction "S7_13") (pintype "bidirectional"))
      (node (ref "R52") (pin "1") (pinfunction "1_1") (pintype "passive"))
    )
    (net (code "53") (name "/S8") (class "Default")
      (node (ref "IC2") (pin "11") (pinfunction "S8_11") (pintype "bidirectional"))
      (node (ref "R68") (pin "1") (pinfunction "1_1") (pintype "passive"))
    )
    (net (code "54") (name "/S9") (class "Default")
      (node (ref "IC2") (pin "9") (pinfunction "S9_9") (pintype "bidirectional"))
      (node (ref "R74") (pin "1") (pinfunction "1_1") (pintype "passive"))
    )
    (net (code "55") (name "/S10") (class "Default")
      (node (ref "IC2") (pin "7") (pinfunction "S10_7") (pintype "bidirectional"))
      (node (ref "R80") (pin "1") (pinfunction "1_1") (pintype "passive"))
    )
    (net (code "56") (name "/S11") (class "Default")
      (node (ref "IC2") (pin "5") (pinfunction "S11_5") (pintype "bidirectional"))
      (node (ref "R87") (pin "1") (pinfunction "1_1") (pintype "passive"))
    )
    (net (code "57") (name "/S12") (class "Default")
      (node (ref "IC2") (pin "3") (pinfunction "S12_3") (pintype "bidirectional"))
      (node (ref "R93") (pin "1") (pinfunction "1_1") (pintype "passive"))
    )
    (net (code "58") (name "/SCK") (class "Default")
      (node (ref "IC2") (pin "42") (pinfunction "SCK_(IPA)_42") (pintype "bidirectional"))
      (node (ref "JP1") (pin "2") (pinfunction "2_2") (pintype "passive"))
      (node (ref "R5") (pin "2") (pinfunction "2_2") (pintype "passive"))
    )
    (net (code "59") (name "/V+") (class "Default")
      (node (ref "C20") (pin "2") (pinfunction "2_2") (pintype "passive"))
      (node (ref "IC2") (pin "1") (pinfunction "V+_1") (pintype "bidirectional"))
      (node (ref "R9") (pin "1") (pinfunction "1_1") (pintype "passive"))
    )
    (net (code "60") (name "/VREF1") (class "Default")
      (node (ref "C1") (pin "1") (pinfunction "1_1") (pintype "passive"))
      (node (ref "IC2") (pin "35") (pinfunction "VREF1_35") (pintype "bidirectional"))
    )
    (net (code "61") (name "/VREF2") (class "Default")
      (node (ref "C4") (pin "1") (pinfunction "1_1") (pintype "passive"))
      (node (ref "IC2") (pin "34") (pinfunction "VREF2_34") (pintype "bidirectional"))
      (node (ref "JP7") (pin "19_THERMO1_IN") (pinfunction "19_THERMO1_IN_19_THERMO1_IN") (pintype "passive"))
      (node (ref "JP7") (pin "20_THERMO2_IN") (pinfunction "20_THERMO2_IN_20_THERMO2_IN") (pintype "passive"))
    )
    (net (code "62") (name "/VTEMP1") (class "Default")
      (node (ref "IC2") (pin "27") (pinfunction "GPIO1_27") (pintype "bidirectional"))
      (node (ref "JP7") (pin "21_THERMO1_OUT") (pinfunction "21_THERMO1_OUT_21_THERMO1_OUT") (pintype "passive"))
      (node (ref "R57") (pin "2") (pinfunction "2_2") (pintype "passive"))
    )
    (net (code "63") (name "/VTEMP2") (class "Default")
      (node (ref "IC2") (pin "28") (pinfunction "GPIO2_28") (pintype "bidirectional"))
      (node (ref "JP7") (pin "22_THERMO2_OUT") (pinfunction "22_THERMO2_OUT_22_THERMO2_OUT") (pintype "passive"))
      (node (ref "R58") (pin "2") (pinfunction "2_2") (pintype "passive"))
    )
    (net (code "64") (name "GND") (class "Default")
      (node (ref "C18") (pin "2") (pinfunction "2_2") (pintype "passive"))
      (node (ref "C2") (pin "-") (pinfunction "-_-") (pintype "passive"))
      (node (ref "C21") (pin "2") (pinfunction "2_2") (pintype "passive"))
      (node (ref "C24") (pin "2") (pinfunction "-_2") (pintype "passive"))
      (node (ref "C3") (pin "2") (pinfunction "2_2") (pintype "passive"))
      (node (ref "D1") (pin "A") (pinfunction "A_A") (pintype "passive"))
      (node (ref "IC1") (pin "3") (pinfunction "GND_1_3") (pintype "bidirectional"))
      (node (ref "IC1") (pin "5") (pinfunction "~{ON}/OFF_5") (pintype "bidirectional"))
      (node (ref "IC1") (pin "6") (pinfunction "GND_2_6") (pintype "bidirectional"))
      (node (ref "JP1") (pin "7") (pinfunction "7_7") (pintype "passive"))
      (node (ref "JP7") (pin "15_TOTAL-") (pinfunction "15_TOTAL-_15_TOTAL-") (pintype "passive"))
      (node (ref "LED4") (pin "C") (pinfunction "C_C") (pintype "passive"))
      (node (ref "R16") (pin "1") (pinfunction "1_1") (pintype "passive"))
      (node (ref "U$2") (pin "JP2.7") (pinfunction "GND_JP2.7") (pintype "power_in"))
    )
    (net (code "65") (name "Net-(C24-+)") (class "Default")
      (node (ref "C18") (pin "1") (pinfunction "1_1") (pintype "passive"))
      (node (ref "C24") (pin "1") (pinfunction "+_1") (pintype "passive"))
      (node (ref "IC1") (pin "1") (pinfunction "VIN_1") (pintype "bidirectional"))
      (node (ref "R19") (pin "1") (pinfunction "1_1") (pintype "passive"))
    )
    (net (code "66") (name "Net-(IC1-OUT)") (class "Default")
      (node (ref "D1") (pin "C") (pinfunction "C_C") (pintype "passive"))
      (node (ref "IC1") (pin "2") (pinfunction "OUT_2") (pintype "bidirectional"))
      (node (ref "L1") (pin "P$1") (pinfunction "1_P$1") (pintype "passive"))
    )
    (net (code "67") (name "Net-(LED1-PadA)") (class "Default")
      (node (ref "LED1") (pin "A") (pinfunction "A_A") (pintype "passive"))
      (node (ref "R53") (pin "1") (pinfunction "1_1") (pintype "passive"))
    )
    (net (code "68") (name "Net-(LED1-PadC)") (class "Default")
      (node (ref "LED1") (pin "C") (pinfunction "C_C") (pintype "passive"))
      (node (ref "LED2") (pin "C") (pinfunction "C_C") (pintype "passive"))
    )
    (net (code "69") (name "Net-(LED2-PadA)") (class "Default")
      (node (ref "LED2") (pin "A") (pinfunction "A_A") (pintype "passive"))
      (node (ref "R54") (pin "1") (pinfunction "1_1") (pintype "passive"))
    )
    (net (code "70") (name "Net-(LED4-PadA)") (class "Default")
      (node (ref "LED4") (pin "A") (pinfunction "A_A") (pintype "passive"))
      (node (ref "R56") (pin "1") (pinfunction "1_1") (pintype "passive"))
    )
    (net (code "71") (name "Net-(LED5-PadC)") (class "Default")
      (node (ref "LED5") (pin "C") (pinfunction "C_C") (pintype "passive"))
      (node (ref "R11") (pin "1") (pinfunction "1_1") (pintype "passive"))
    )
    (net (code "72") (name "Net-(LED6-PadC)") (class "Default")
      (node (ref "LED6") (pin "C") (pinfunction "C_C") (pintype "passive"))
      (node (ref "R23") (pin "1") (pinfunction "1_1") (pintype "passive"))
    )
    (net (code "73") (name "Net-(LED7-PadC)") (class "Default")
      (node (ref "LED7") (pin "C") (pinfunction "C_C") (pintype "passive"))
      (node (ref "R29") (pin "1") (pinfunction "1_1") (pintype "passive"))
    )
    (net (code "74") (name "Net-(LED8-PadC)") (class "Default")
      (node (ref "LED8") (pin "C") (pinfunction "C_C") (pintype "passive"))
      (node (ref "R35") (pin "1") (pinfunction "1_1") (pintype "passive"))
    )
    (net (code "75") (name "Net-(LED9-PadC)") (class "Default")
      (node (ref "LED9") (pin "C") (pinfunction "C_C") (pintype "passive"))
      (node (ref "R41") (pin "1") (pinfunction "1_1") (pintype "passive"))
    )
    (net (code "76") (name "Net-(LED11-PadC)") (class "Default")
      (node (ref "LED11") (pin "C") (pinfunction "C_C") (pintype "passive"))
      (node (ref "R47") (pin "1") (pinfunction "1_1") (pintype "passive"))
    )
    (net (code "77") (name "Net-(LED12-PadC)") (class "Default")
      (node (ref "LED12") (pin "C") (pinfunction "C_C") (pintype "passive"))
      (node (ref "R63") (pin "1") (pinfunction "1_1") (pintype "passive"))
    )
    (net (code "78") (name "Net-(LED13-PadC)") (class "Default")
      (node (ref "LED13") (pin "C") (pinfunction "C_C") (pintype "passive"))
      (node (ref "R69") (pin "1") (pinfunction "1_1") (pintype "passive"))
    )
    (net (code "79") (name "Net-(LED14-PadC)") (class "Default")
      (node (ref "LED14") (pin "C") (pinfunction "C_C") (pintype "passive"))
      (node (ref "R75") (pin "1") (pinfunction "1_1") (pintype "passive"))
    )
    (net (code "80") (name "Net-(LED15-PadC)") (class "Default")
      (node (ref "LED15") (pin "C") (pinfunction "C_C") (pintype "passive"))
      (node (ref "R81") (pin "1") (pinfunction "1_1") (pintype "passive"))
    )
    (net (code "81") (name "Net-(LED16-PadC)") (class "Default")
      (node (ref "LED16") (pin "C") (pinfunction "C_C") (pintype "passive"))
      (node (ref "R88") (pin "1") (pinfunction "1_1") (pintype "passive"))
    )
    (net (code "82") (name "Net-(LED17-PadC)") (class "Default")
      (node (ref "LED17") (pin "C") (pinfunction "C_C") (pintype "passive"))
      (node (ref "R94") (pin "1") (pinfunction "1_1") (pintype "passive"))
    )
    (net (code "83") (name "Net-(Q2-D)") (class "Default")
      (node (ref "LED5") (pin "A") (pinfunction "A_A") (pintype "passive"))
      (node (ref "Q2") (pin "3") (pinfunction "D_3") (pintype "bidirectional"))
      (node (ref "R8") (pin "2") (pinfunction "2_2") (pintype "passive"))
    )
    (net (code "84") (name "Net-(Q2-G)") (class "Default")
      (node (ref "Q2") (pin "1") (pinfunction "G_1") (pintype "bidirectional"))
      (node (ref "R10") (pin "2") (pinfunction "2_2") (pintype "passive"))
    )
    (net (code "85") (name "Net-(Q3-D)") (class "Default")
      (node (ref "LED6") (pin "A") (pinfunction "A_A") (pintype "passive"))
      (node (ref "Q3") (pin "3") (pinfunction "D_3") (pintype "bidirectional"))
      (node (ref "R21") (pin "2") (pinfunction "2_2") (pintype "passive"))
    )
    (net (code "86") (name "Net-(Q3-G)") (class "Default")
      (node (ref "Q3") (pin "1") (pinfunction "G_1") (pintype "bidirectional"))
      (node (ref "R22") (pin "2") (pinfunction "2_2") (pintype "passive"))
    )
    (net (code "87") (name "Net-(Q4-D)") (class "Default")
      (node (ref "LED7") (pin "A") (pinfunction "A_A") (pintype "passive"))
      (node (ref "Q4") (pin "3") (pinfunction "D_3") (pintype "bidirectional"))
      (node (ref "R27") (pin "2") (pinfunction "2_2") (pintype "passive"))
    )
    (net (code "88") (name "Net-(Q4-G)") (class "Default")
      (node (ref "Q4") (pin "1") (pinfunction "G_1") (pintype "bidirectional"))
      (node (ref "R28") (pin "2") (pinfunction "2_2") (pintype "passive"))
    )
    (net (code "89") (name "Net-(Q5-D)") (class "Default")
      (node (ref "LED8") (pin "A") (pinfunction "A_A") (pintype "passive"))
      (node (ref "Q5") (pin "3") (pinfunction "D_3") (pintype "bidirectional"))
      (node (ref "R33") (pin "2") (pinfunction "2_2") (pintype "passive"))
    )
    (net (code "90") (name "Net-(Q5-G)") (class "Default")
      (node (ref "Q5") (pin "1") (pinfunction "G_1") (pintype "bidirectional"))
      (node (ref "R34") (pin "2") (pinfunction "2_2") (pintype "passive"))
    )
    (net (code "91") (name "Net-(Q6-D)") (class "Default")
      (node (ref "LED9") (pin "A") (pinfunction "A_A") (pintype "passive"))
      (node (ref "Q6") (pin "3") (pinfunction "D_3") (pintype "bidirectional"))
      (node (ref "R39") (pin "2") (pinfunction "2_2") (pintype "passive"))
    )
    (net (code "92") (name "Net-(Q6-G)") (class "Default")
      (node (ref "Q6") (pin "1") (pinfunction "G_1") (pintype "bidirectional"))
      (node (ref "R40") (pin "2") (pinfunction "2_2") (pintype "passive"))
    )
    (net (code "93") (name "Net-(Q7-D)") (class "Default")
      (node (ref "LED11") (pin "A") (pinfunction "A_A") (pintype "passive"))
      (node (ref "Q7") (pin "3") (pinfunction "D_3") (pintype "bidirectional"))
      (node (ref "R45") (pin "2") (pinfunction "2_2") (pintype "passive"))
    )
    (net (code "94") (name "Net-(Q7-G)") (class "Default")
      (node (ref "Q7") (pin "1") (pinfunction "G_1") (pintype "bidirectional"))
      (node (ref "R46") (pin "2") (pinfunction "2_2") (pintype "passive"))
    )
    (net (code "95") (name "Net-(Q8-D)") (class "Default")
      (node (ref "LED12") (pin "A") (pinfunction "A_A") (pintype "passive"))
      (node (ref "Q8") (pin "3") (pinfunction "D_3") (pintype "bidirectional"))
      (node (ref "R51") (pin "2") (pinfunction "2_2") (pintype "passive"))
    )
    (net (code "96") (name "Net-(Q8-G)") (class "Default")
      (node (ref "Q8") (pin "1") (pinfunction "G_1") (pintype "bidirectional"))
      (node (ref "R52") (pin "2") (pinfunction "2_2") (pintype "passive"))
    )
    (net (code "97") (name "Net-(Q9-D)") (class "Default")
      (node (ref "LED13") (pin "A") (pinfunction "A_A") (pintype "passive"))
      (node (ref "Q9") (pin "3") (pinfunction "D_3") (pintype "bidirectional"))
      (node (ref "R67") (pin "2") (pinfunction "2_2") (pintype "passive"))
    )
    (net (code "98") (name "Net-(Q9-G)") (class "Default")
      (node (ref "Q9") (pin "1") (pinfunction "G_1") (pintype "bidirectional"))
      (node (ref "R68") (pin "2") (pinfunction "2_2") (pintype "passive"))
    )
    (net (code "99") (name "Net-(Q10-D)") (class "Default")
      (node (ref "LED14") (pin "A") (pinfunction "A_A") (pintype "passive"))
      (node (ref "Q10") (pin "3") (pinfunction "D_3") (pintype "bidirectional"))
      (node (ref "R73") (pin "2") (pinfunction "2_2") (pintype "passive"))
    )
    (net (code "100") (name "Net-(Q10-G)") (class "Default")
      (node (ref "Q10") (pin "1") (pinfunction "G_1") (pintype "bidirectional"))
      (node (ref "R74") (pin "2") (pinfunction "2_2") (pintype "passive"))
    )
    (net (code "101") (name "Net-(Q11-D)") (class "Default")
      (node (ref "LED15") (pin "A") (pinfunction "A_A") (pintype "passive"))
      (node (ref "Q11") (pin "3") (pinfunction "D_3") (pintype "bidirectional"))
      (node (ref "R79") (pin "2") (pinfunction "2_2") (pintype "passive"))
    )
    (net (code "102") (name "Net-(Q11-G)") (class "Default")
      (node (ref "Q11") (pin "1") (pinfunction "G_1") (pintype "bidirectional"))
      (node (ref "R80") (pin "2") (pinfunction "2_2") (pintype "passive"))
    )
    (net (code "103") (name "Net-(Q12-D)") (class "Default")
      (node (ref "LED16") (pin "A") (pinfunction "A_A") (pintype "passive"))
      (node (ref "Q12") (pin "3") (pinfunction "D_3") (pintype "bidirectional"))
      (node (ref "R86") (pin "2") (pinfunction "2_2") (pintype "passive"))
    )
    (net (code "104") (name "Net-(Q12-G)") (class "Default")
      (node (ref "Q12") (pin "1") (pinfunction "G_1") (pintype "bidirectional"))
      (node (ref "R87") (pin "2") (pinfunction "2_2") (pintype "passive"))
    )
    (net (code "105") (name "Net-(Q13-D)") (class "Default")
      (node (ref "LED17") (pin "A") (pinfunction "A_A") (pintype "passive"))
      (node (ref "Q13") (pin "3") (pinfunction "D_3") (pintype "bidirectional"))
      (node (ref "R92") (pin "2") (pinfunction "2_2") (pintype "passive"))
    )
    (net (code "106") (name "Net-(Q13-G)") (class "Default")
      (node (ref "Q13") (pin "1") (pinfunction "G_1") (pintype "bidirectional"))
      (node (ref "R93") (pin "2") (pinfunction "2_2") (pintype "passive"))
    )
    (net (code "107") (name "Net-(R4-Pad2)") (class "Default")
      (node (ref "R4") (pin "2") (pinfunction "2_2") (pintype "passive"))
      (node (ref "R7") (pin "1") (pinfunction "1_1") (pintype "passive"))
    )
    (net (code "108") (name "Net-(R7-Pad2)") (class "Default")
      (node (ref "R7") (pin "2") (pinfunction "2_2") (pintype "passive"))
      (node (ref "R8") (pin "1") (pinfunction "1_1") (pintype "passive"))
    )
    (net (code "109") (name "Net-(R14-Pad2)") (class "Default")
      (node (ref "R14") (pin "2") (pinfunction "2_2") (pintype "passive"))
      (node (ref "R20") (pin "1") (pinfunction "1_1") (pintype "passive"))
    )
    (net (code "110") (name "Net-(R20-Pad2)") (class "Default")
      (node (ref "R20") (pin "2") (pinfunction "2_2") (pintype "passive"))
      (node (ref "R21") (pin "1") (pinfunction "1_1") (pintype "passive"))
    )
    (net (code "111") (name "Net-(R25-Pad2)") (class "Default")
      (node (ref "R25") (pin "2") (pinfunction "2_2") (pintype "passive"))
      (node (ref "R26") (pin "1") (pinfunction "1_1") (pintype "passive"))
    )
    (net (code "112") (name "Net-(R26-Pad2)") (class "Default")
      (node (ref "R26") (pin "2") (pinfunction "2_2") (pintype "passive"))
      (node (ref "R27") (pin "1") (pinfunction "1_1") (pintype "passive"))
    )
    (net (code "113") (name "Net-(R31-Pad2)") (class "Default")
      (node (ref "R31") (pin "2") (pinfunction "2_2") (pintype "passive"))
      (node (ref "R32") (pin "1") (pinfunction "1_1") (pintype "passive"))
    )
    (net (code "114") (name "Net-(R32-Pad2)") (class "Default")
      (node (ref "R32") (pin "2") (pinfunction "2_2") (pintype "passive"))
      (node (ref "R33") (pin "1") (pinfunction "1_1") (pintype "passive"))
    )
    (net (code "115") (name "Net-(R37-Pad2)") (class "Default")
      (node (ref "R37") (pin "2") (pinfunction "2_2") (pintype "passive"))
      (node (ref "R38") (pin "1") (pinfunction "1_1") (pintype "passive"))
    )
    (net (code "116") (name "Net-(R38-Pad2)") (class "Default")
      (node (ref "R38") (pin "2") (pinfunction "2_2") (pintype "passive"))
      (node (ref "R39") (pin "1") (pinfunction "1_1") (pintype "passive"))
    )
    (net (code "117") (name "Net-(R43-Pad2)") (class "Default")
      (node (ref "R43") (pin "2") (pinfunction "2_2") (pintype "passive"))
      (node (ref "R44") (pin "1") (pinfunction "1_1") (pintype "passive"))
    )
    (net (code "118") (name "Net-(R44-Pad2)") (class "Default")
      (node (ref "R44") (pin "2") (pinfunction "2_2") (pintype "passive"))
      (node (ref "R45") (pin "1") (pinfunction "1_1") (pintype "passive"))
    )
    (net (code "119") (name "Net-(R49-Pad2)") (class "Default")
      (node (ref "R49") (pin "2") (pinfunction "2_2") (pintype "passive"))
      (node (ref "R50") (pin "1") (pinfunction "1_1") (pintype "passive"))
    )
    (net (code "120") (name "Net-(R50-Pad2)") (class "Default")
      (node (ref "R50") (pin "2") (pinfunction "2_2") (pintype "passive"))
      (node (ref "R51") (pin "1") (pinfunction "1_1") (pintype "passive"))
    )
    (net (code "121") (name "Net-(R65-Pad2)") (class "Default")
      (node (ref "R65") (pin "2") (pinfunction "2_2") (pintype "passive"))
      (node (ref "R66") (pin "1") (pinfunction "1_1") (pintype "passive"))
    )
    (net (code "122") (name "Net-(R66-Pad2)") (class "Default")
      (node (ref "R66") (pin "2") (pinfunction "2_2") (pintype "passive"))
      (node (ref "R67") (pin "1") (pinfunction "1_1") (pintype "passive"))
    )
    (net (code "123") (name "Net-(R71-Pad2)") (class "Default")
      (node (ref "R71") (pin "2") (pinfunction "2_2") (pintype "passive"))
      (node (ref "R72") (pin "1") (pinfunction "1_1") (pintype "passive"))
    )
    (net (code "124") (name "Net-(R72-Pad2)") (class "Default")
      (node (ref "R72") (pin "2") (pinfunction "2_2") (pintype "passive"))
      (node (ref "R73") (pin "1") (pinfunction "1_1") (pintype "passive"))
    )
    (net (code "125") (name "Net-(R77-Pad2)") (class "Default")
      (node (ref "R77") (pin "2") (pinfunction "2_2") (pintype "passive"))
      (node (ref "R78") (pin "1") (pinfunction "1_1") (pintype "passive"))
    )
    (net (code "126") (name "Net-(R78-Pad2)") (class "Default")
      (node (ref "R78") (pin "2") (pinfunction "2_2") (pintype "passive"))
      (node (ref "R79") (pin "1") (pinfunction "1_1") (pintype "passive"))
    )
    (net (code "127") (name "Net-(R84-Pad2)") (class "Default")
      (node (ref "R84") (pin "2") (pinfunction "2_2") (pintype "passive"))
      (node (ref "R85") (pin "1") (pinfunction "1_1") (pintype "passive"))
    )
    (net (code "128") (name "Net-(R85-Pad2)") (class "Default")
      (node (ref "R85") (pin "2") (pinfunction "2_2") (pintype "passive"))
      (node (ref "R86") (pin "1") (pinfunction "1_1") (pintype "passive"))
    )
    (net (code "129") (name "Net-(R90-Pad2)") (class "Default")
      (node (ref "R90") (pin "2") (pinfunction "2_2") (pintype "passive"))
      (node (ref "R91") (pin "1") (pinfunction "1_1") (pintype "passive"))
    )
    (net (code "130") (name "Net-(R91-Pad2)") (class "Default")
      (node (ref "R91") (pin "2") (pinfunction "2_2") (pintype "passive"))
      (node (ref "R92") (pin "1") (pinfunction "1_1") (pintype "passive"))
    )
    (net (code "131") (name "Net-(T1-D)") (class "Default")
      (node (ref "R59") (pin "1") (pinfunction "1_1") (pintype "passive"))
      (node (ref "T1") (pin "1") (pinfunction "D_1") (pintype "passive"))
    )
    (net (code "132") (name "Net-(T1-S)") (class "Default")
      (node (ref "R55") (pin "1") (pinfunction "1_1") (pintype "passive"))
      (node (ref "T1") (pin "2") (pinfunction "S_2") (pintype "passive"))
    )
    (net (code "133") (name "Net-(U$2-D1)") (class "Default")
      (node (ref "R53") (pin "2") (pinfunction "2_2") (pintype "passive"))
      (node (ref "U$2") (pin "JP2.3") (pinfunction "D1_JP2.3") (pintype "bidirectional"))
    )
    (net (code "134") (name "Net-(U$2-D2)") (class "Default")
      (node (ref "R54") (pin "2") (pinfunction "2_2") (pintype "passive"))
      (node (ref "U$2") (pin "JP2.4") (pinfunction "D2_JP2.4") (pintype "bidirectional"))
    )
    (net (code "135") (name "Net-(U$2-D4)") (class "Default")
      (node (ref "R56") (pin "2") (pinfunction "2_2") (pintype "passive"))
      (node (ref "U$2") (pin "JP2.6") (pinfunction "D4_JP2.6") (pintype "bidirectional"))
    )
    (net (code "136") (name "Net-(U$2-D5)") (class "Default")
      (node (ref "R5") (pin "1") (pinfunction "1_1") (pintype "passive"))
      (node (ref "U$2") (pin "JP1.4") (pinfunction "D5_JP1.4") (pintype "bidirectional"))
    )
    (net (code "137") (name "Net-(U$2-D6)") (class "Default")
      (node (ref "R61") (pin "1") (pinfunction "1_1") (pintype "passive"))
      (node (ref "U$2") (pin "JP1.5") (pinfunction "D6_JP1.5") (pintype "bidirectional"))
    )
    (net (code "138") (name "Net-(U$2-D7)") (class "Default")
      (node (ref "R62") (pin "1") (pinfunction "1_1") (pintype "passive"))
      (node (ref "U$2") (pin "JP1.6") (pinfunction "D7_JP1.6") (pintype "bidirectional"))
    )
    (net (code "139") (name "Net-(U$2-D8)") (class "Default")
      (node (ref "R6") (pin "1") (pinfunction "1_1") (pintype "passive"))
      (node (ref "U$2") (pin "JP1.7") (pinfunction "D8_JP1.7") (pintype "bidirectional"))
    )
    (net (code "140") (name "unconnected-(IC2-DRIVE-Pad38)") (class "Default")
      (node (ref "IC2") (pin "38") (pinfunction "DRIVE_38") (pintype "bidirectional"))
    )
    (net (code "141") (name "unconnected-(IC2-WDT-Pad39)") (class "Default")
      (node (ref "IC2") (pin "39") (pinfunction "WDT_39") (pintype "bidirectional"))
    )
    (net (code "142") (name "unconnected-(JP7-Pad9)") (class "Default")
      (node (ref "JP7") (pin "9") (pinfunction "9_9") (pintype "passive"))
    )
    (net (code "143") (name "unconnected-(JP7-Pad12)") (class "Default")
      (node (ref "JP7") (pin "12") (pinfunction "12_12") (pintype "passive"))
    )
    (net (code "144") (name "unconnected-(JP7-Pad18)") (class "Default")
      (node (ref "JP7") (pin "18") (pinfunction "18_18") (pintype "passive"))
    )
    (net (code "145") (name "unconnected-(U$2-RX-PadJP2.2)") (class "Default")
      (node (ref "U$2") (pin "JP2.2") (pinfunction "RX_JP2.2") (pintype "bidirectional"))
    )
    (net (code "146") (name "unconnected-(U$2-TX-PadJP2.1)") (class "Default")
      (node (ref "U$2") (pin "JP2.1") (pinfunction "TX_JP2.1") (pintype "bidirectional"))
    )
  )
)
